# ProDoc_Custom_Keyboard_2025-10-20.net
KiCad netlist of a schematic drawn in EasyEDA Pro
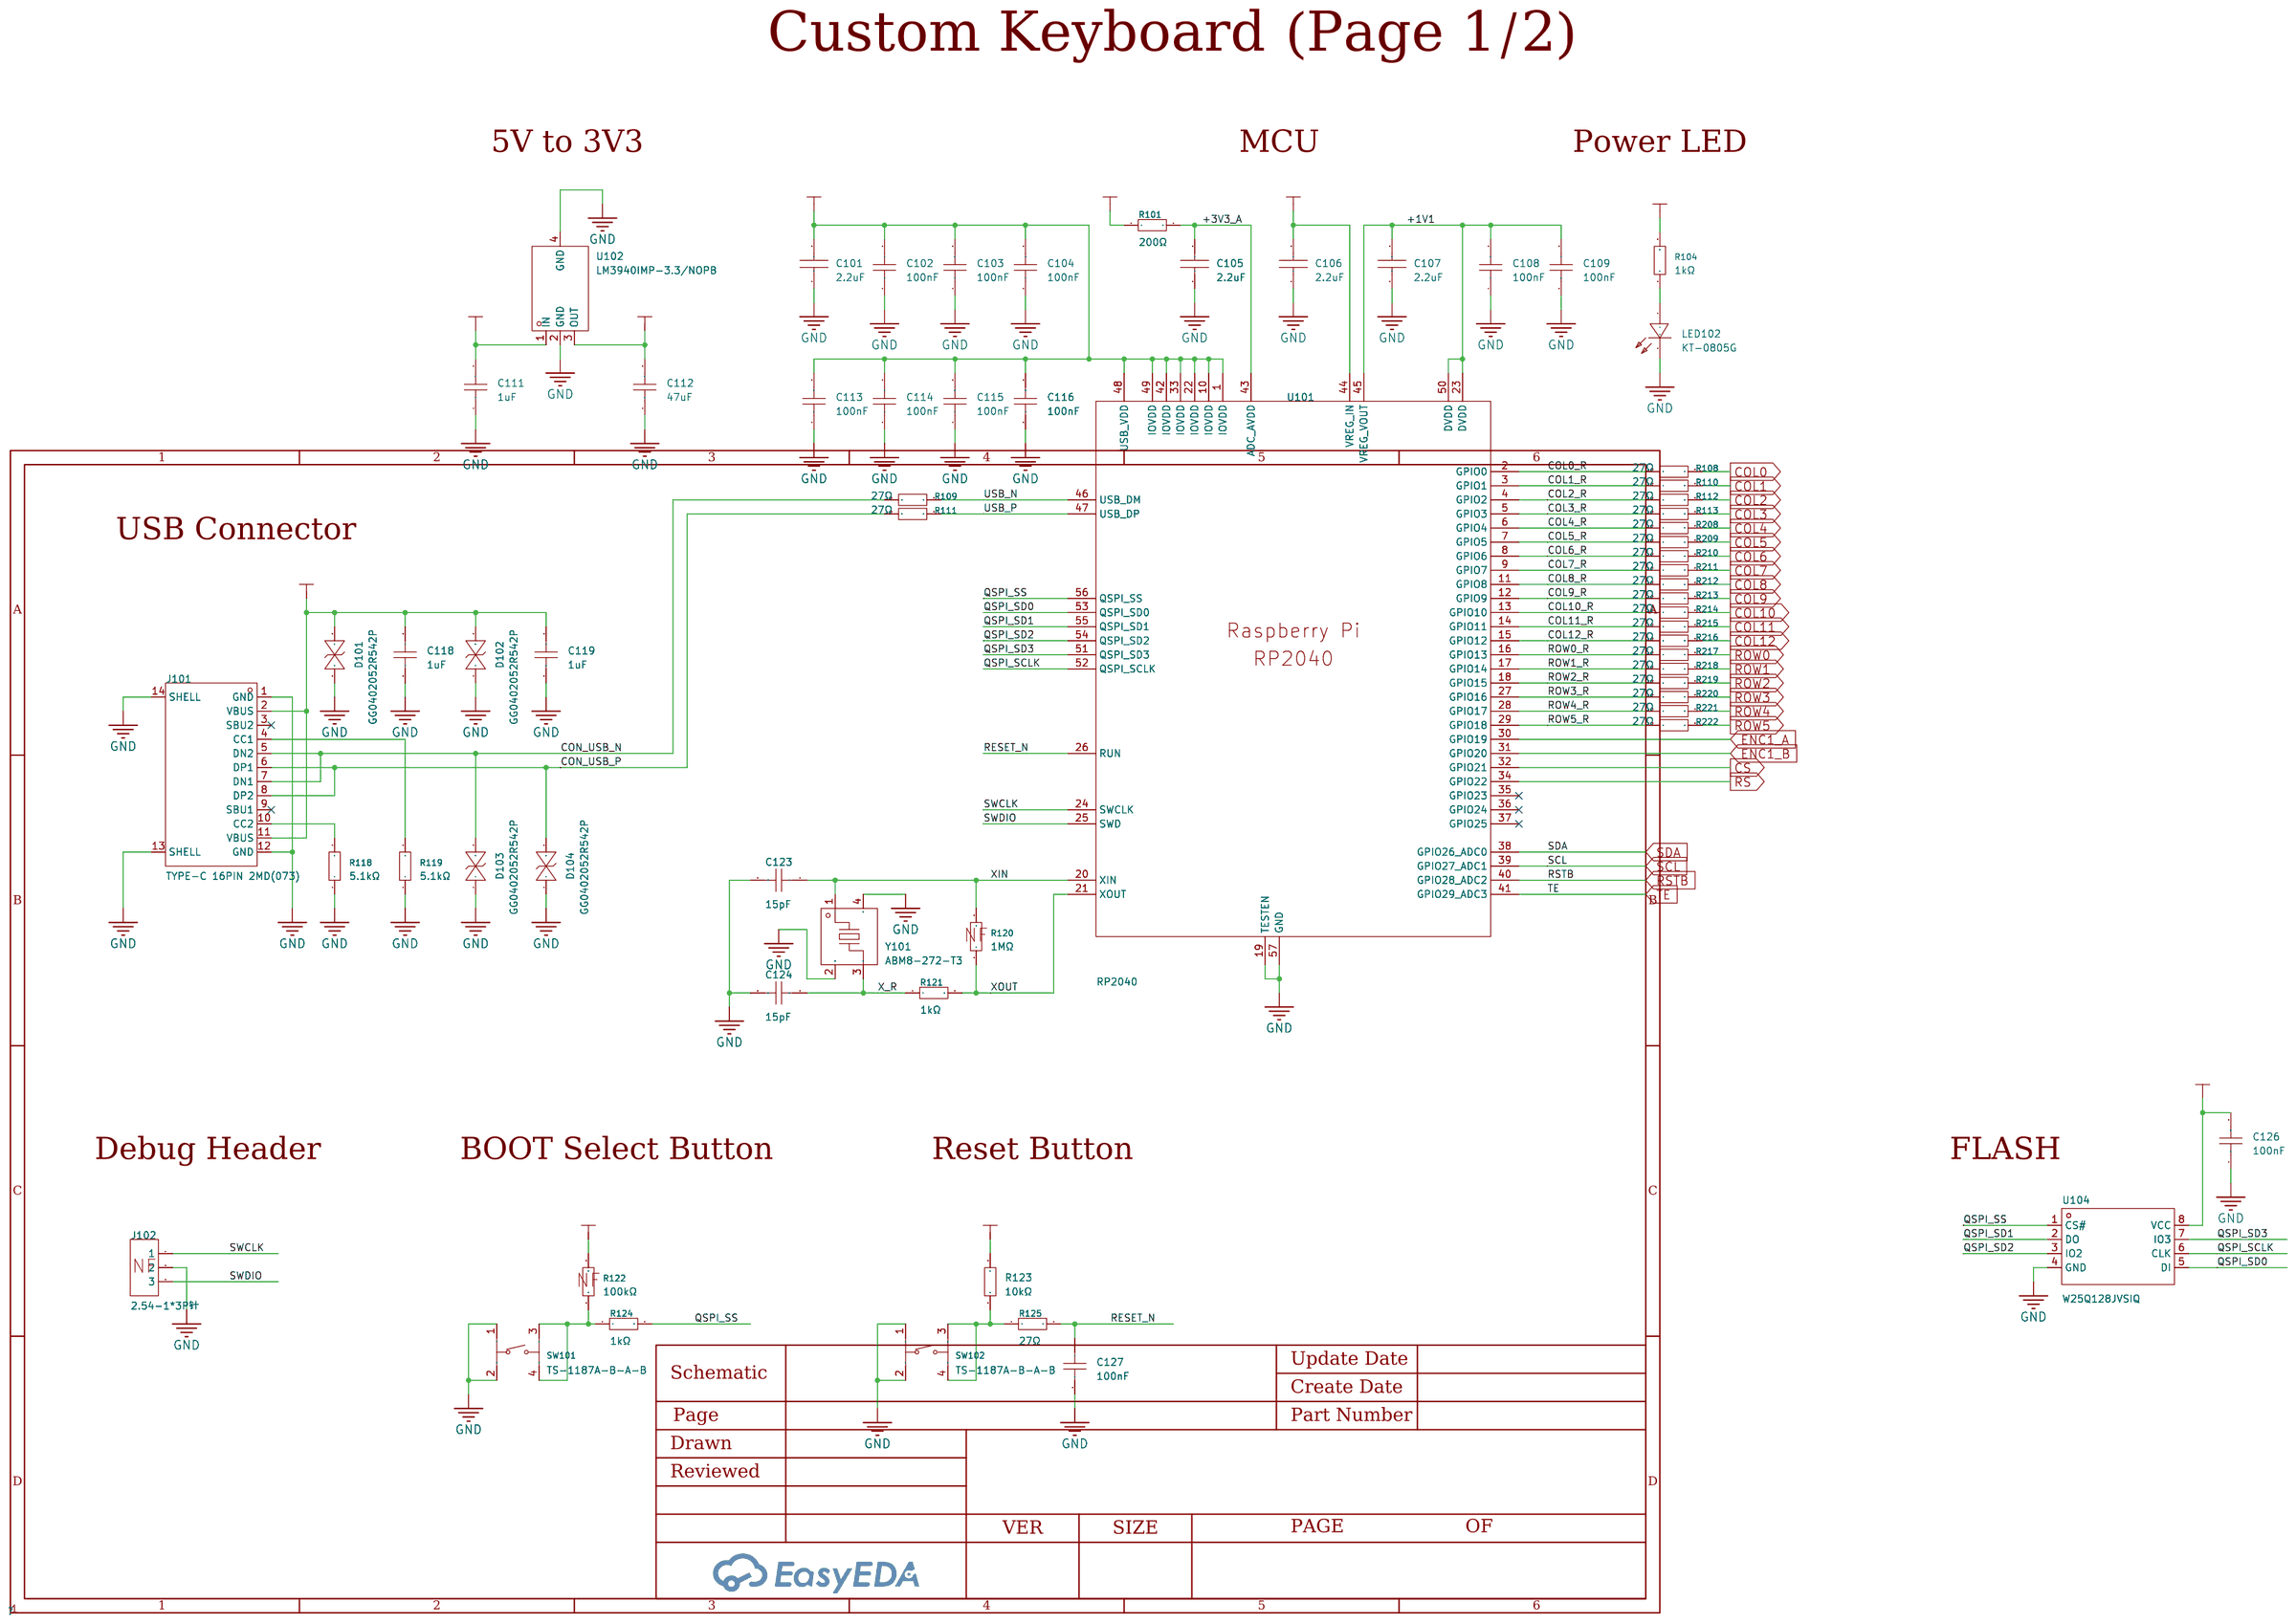
[diagram p0: MCU]
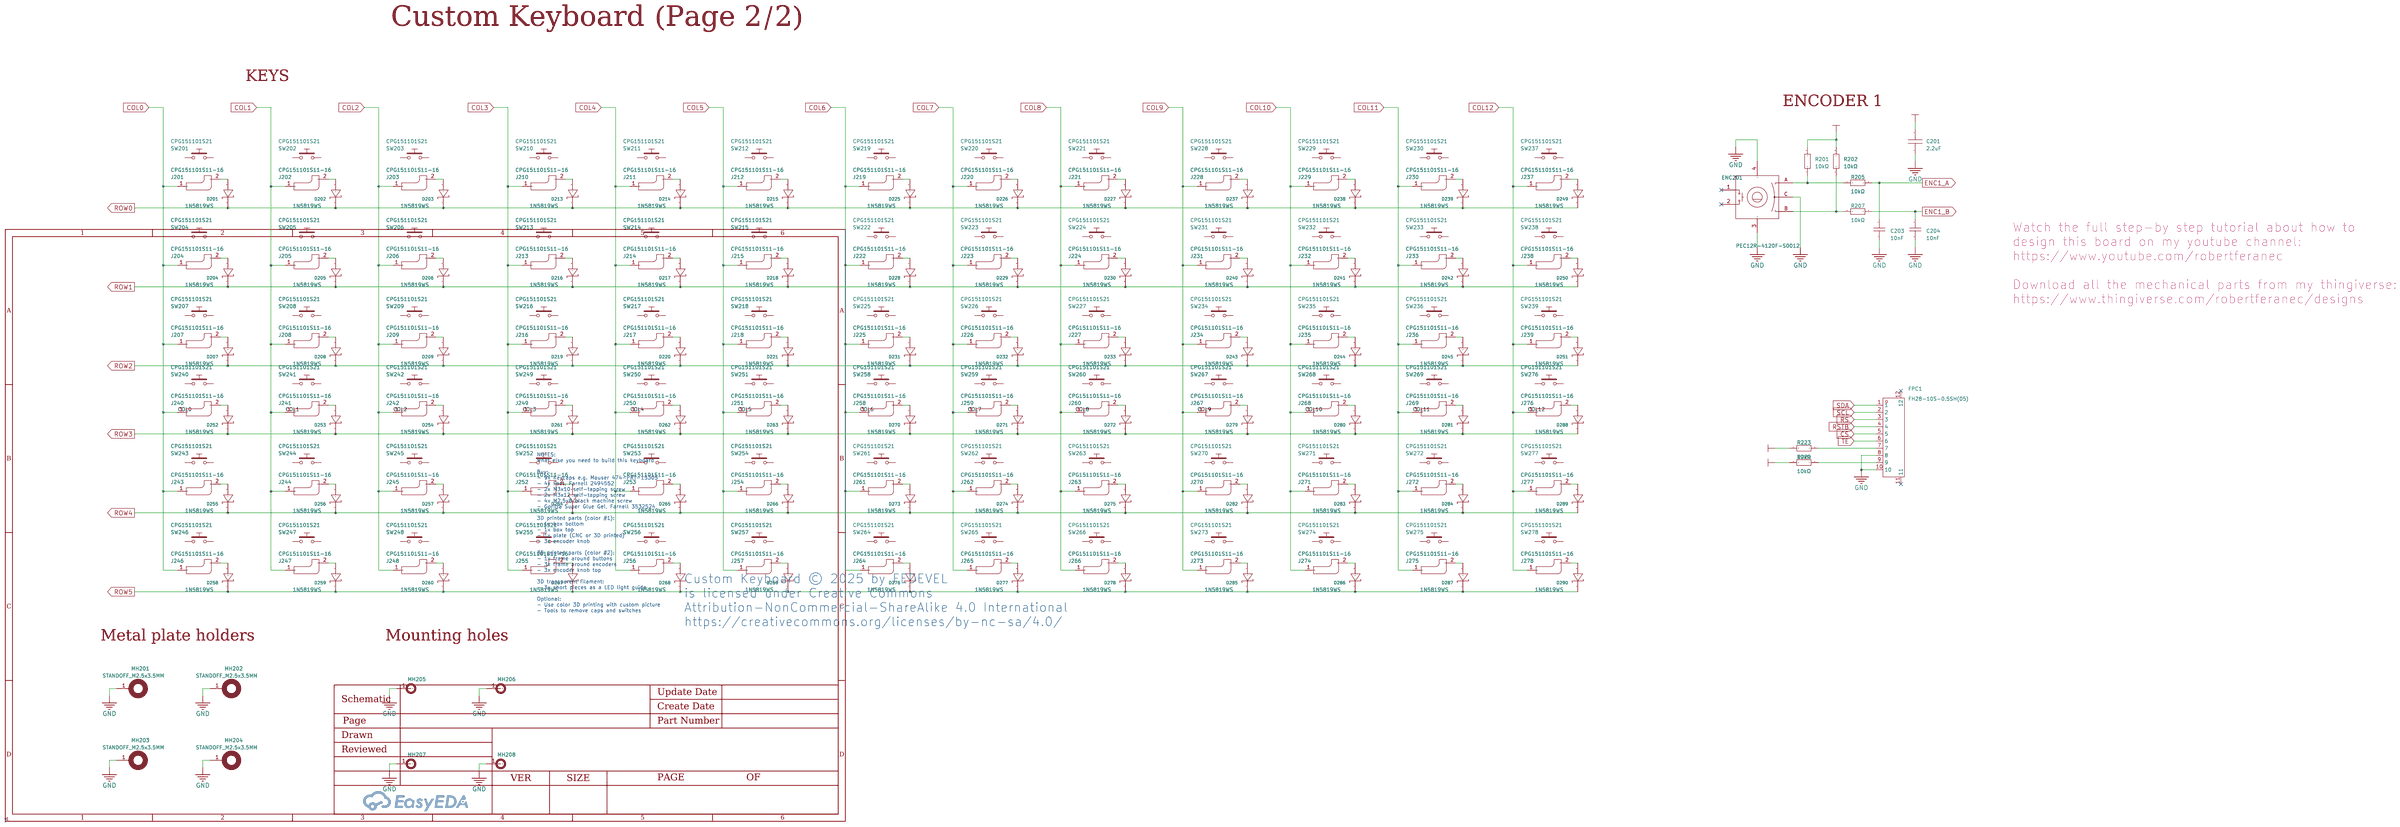
[diagram p1: OTHER]

(export (version "E")
  (design (tool "Eeschema 10.0.6"))
  (components
    (comp (ref "C101")
      (value "2.2uF")
      (footprint "easyedapro:C0402")
      (fields
        (field (name "Manufacturer Part") "CL05A225MQ5NSNC")
        (field (name "Manufacturer") "SAMSUNG(三星)")
      )
      (libsource (lib "easyedapro") (part "CL05A225MQ5NSNC"))
    )
    (comp (ref "C102")
      (value "100nF")
      (footprint "easyedapro:C0402")
      (fields
        (field (name "Manufacturer Part") "CL05B104KO5NNNC")
        (field (name "Manufacturer") "SAMSUNG(三星)")
      )
      (libsource (lib "easyedapro") (part "CL05B104KO5NNNC"))
    )
    (comp (ref "C103")
      (value "100nF")
      (footprint "easyedapro:C0402")
      (fields
        (field (name "Manufacturer Part") "CL05B104KO5NNNC")
        (field (name "Manufacturer") "SAMSUNG(三星)")
      )
      (libsource (lib "easyedapro") (part "CL05B104KO5NNNC"))
    )
    (comp (ref "C104")
      (value "100nF")
      (footprint "easyedapro:C0402")
      (fields
        (field (name "Manufacturer Part") "CL05B104KO5NNNC")
        (field (name "Manufacturer") "SAMSUNG(三星)")
      )
      (libsource (lib "easyedapro") (part "CL05B104KO5NNNC"))
    )
    (comp (ref "C105")
      (value "2.2uF")
      (footprint "easyedapro:C0402")
      (fields
        (field (name "Manufacturer Part") "CL05A225MQ5NSNC")
        (field (name "Manufacturer") "SAMSUNG(三星)")
      )
      (libsource (lib "easyedapro") (part "CL05A225MQ5NSNC"))
    )
    (comp (ref "C106")
      (value "2.2uF")
      (footprint "easyedapro:C0402")
      (fields
        (field (name "Manufacturer Part") "CL05A225MQ5NSNC")
        (field (name "Manufacturer") "SAMSUNG(三星)")
      )
      (libsource (lib "easyedapro") (part "CL05A225MQ5NSNC"))
    )
    (comp (ref "C107")
      (value "2.2uF")
      (footprint "easyedapro:C0402")
      (fields
        (field (name "Manufacturer Part") "CL05A225MQ5NSNC")
        (field (name "Manufacturer") "SAMSUNG(三星)")
      )
      (libsource (lib "easyedapro") (part "CL05A225MQ5NSNC"))
    )
    (comp (ref "C108")
      (value "100nF")
      (footprint "easyedapro:C0402")
      (fields
        (field (name "Manufacturer Part") "CL05B104KO5NNNC")
        (field (name "Manufacturer") "SAMSUNG(三星)")
      )
      (libsource (lib "easyedapro") (part "CL05B104KO5NNNC"))
    )
    (comp (ref "C109")
      (value "100nF")
      (footprint "easyedapro:C0402")
      (fields
        (field (name "Manufacturer Part") "CL05B104KO5NNNC")
        (field (name "Manufacturer") "SAMSUNG(三星)")
      )
      (libsource (lib "easyedapro") (part "CL05B104KO5NNNC"))
    )
    (comp (ref "C111")
      (value "1uF")
      (footprint "easyedapro:C0402")
      (fields
        (field (name "Manufacturer Part") "CL05A105KA5NQNC")
        (field (name "Manufacturer") "SAMSUNG(三星)")
      )
      (libsource (lib "easyedapro") (part "CL05A105KA5NQNC"))
    )
    (comp (ref "C112")
      (value "47uF")
      (footprint "easyedapro:C1206")
      (fields
        (field (name "Manufacturer Part") "CL31A476MPHNNNE")
        (field (name "Manufacturer") "SAMSUNG(三星)")
      )
      (libsource (lib "easyedapro") (part "CL31A476MPHNNNE"))
    )
    (comp (ref "C113")
      (value "100nF")
      (footprint "easyedapro:C0402")
      (fields
        (field (name "Manufacturer Part") "CL05B104KO5NNNC")
        (field (name "Manufacturer") "SAMSUNG(三星)")
      )
      (libsource (lib "easyedapro") (part "CL05B104KO5NNNC"))
    )
    (comp (ref "C114")
      (value "100nF")
      (footprint "easyedapro:C0402")
      (fields
        (field (name "Manufacturer Part") "CL05B104KO5NNNC")
        (field (name "Manufacturer") "SAMSUNG(三星)")
      )
      (libsource (lib "easyedapro") (part "CL05B104KO5NNNC"))
    )
    (comp (ref "C115")
      (value "100nF")
      (footprint "easyedapro:C0402")
      (fields
        (field (name "Manufacturer Part") "CL05B104KO5NNNC")
        (field (name "Manufacturer") "SAMSUNG(三星)")
      )
      (libsource (lib "easyedapro") (part "CL05B104KO5NNNC"))
    )
    (comp (ref "C116")
      (value "100nF")
      (footprint "easyedapro:C0402")
      (fields
        (field (name "Manufacturer Part") "CL05B104KO5NNNC")
        (field (name "Manufacturer") "SAMSUNG(三星)")
      )
      (libsource (lib "easyedapro") (part "CL05B104KO5NNNC"))
    )
    (comp (ref "C118")
      (value "1uF")
      (footprint "easyedapro:C0402")
      (fields
        (field (name "Manufacturer Part") "CL05A105KA5NQNC")
        (field (name "Manufacturer") "SAMSUNG(三星)")
      )
      (libsource (lib "easyedapro") (part "CL05A105KA5NQNC"))
    )
    (comp (ref "C119")
      (value "1uF")
      (footprint "easyedapro:C0402")
      (fields
        (field (name "Manufacturer Part") "CL05A105KA5NQNC")
        (field (name "Manufacturer") "SAMSUNG(三星)")
      )
      (libsource (lib "easyedapro") (part "CL05A105KA5NQNC"))
    )
    (comp (ref "C123")
      (value "15pF")
      (footprint "easyedapro:C0402")
      (fields
        (field (name "Manufacturer Part") "CL05C150JB5NNNC")
        (field (name "Manufacturer") "SAMSUNG(三星)")
      )
      (libsource (lib "easyedapro") (part "CL05C150JB5NNNC"))
    )
    (comp (ref "C124")
      (value "15pF")
      (footprint "easyedapro:C0402")
      (fields
        (field (name "Manufacturer Part") "CL05C150JB5NNNC")
        (field (name "Manufacturer") "SAMSUNG(三星)")
      )
      (libsource (lib "easyedapro") (part "CL05C150JB5NNNC"))
    )
    (comp (ref "C126")
      (value "100nF")
      (footprint "easyedapro:C0402")
      (fields
        (field (name "Manufacturer Part") "CL05B104KO5NNNC")
        (field (name "Manufacturer") "SAMSUNG(三星)")
      )
      (libsource (lib "easyedapro") (part "CL05B104KO5NNNC"))
    )
    (comp (ref "C127")
      (value "100nF")
      (footprint "easyedapro:C0402")
      (fields
        (field (name "Manufacturer Part") "CL05B104KO5NNNC")
        (field (name "Manufacturer") "SAMSUNG(三星)")
      )
      (libsource (lib "easyedapro") (part "CL05B104KO5NNNC"))
    )
    (comp (ref "D101")
      (value "GG0402052R542P")
      (footprint "easyedapro:D0402-BI")
      (fields (field (name "Manufacturer") "Kyocera AVX"))
      (libsource (lib "easyedapro") (part "GG0402052R542P"))
    )
    (comp (ref "D102")
      (value "GG0402052R542P")
      (footprint "easyedapro:D0402-BI")
      (fields (field (name "Manufacturer") "Kyocera AVX"))
      (libsource (lib "easyedapro") (part "GG0402052R542P"))
    )
    (comp (ref "D103")
      (value "GG0402052R542P")
      (footprint "easyedapro:D0402-BI")
      (fields (field (name "Manufacturer") "Kyocera AVX"))
      (libsource (lib "easyedapro") (part "GG0402052R542P"))
    )
    (comp (ref "D104")
      (value "GG0402052R542P")
      (footprint "easyedapro:D0402-BI")
      (fields (field (name "Manufacturer") "Kyocera AVX"))
      (libsource (lib "easyedapro") (part "GG0402052R542P"))
    )
    (comp (ref "J101")
      (value "TYPE-C 16PIN 2MD(073)")
      (footprint "easyedapro:USB-C-SMD_TYPE-C-6PIN-2MD-073")
      (fields (field (name "Manufacturer") "SHOU HAN(首韩)"))
      (libsource (lib "easyedapro") (part "TYPE-C 16PIN 2MD(073)"))
    )
    (comp (ref "J102")
      (value "2.54-1*3P针")
      (footprint "easyedapro:HDR-TH_3P-P2.54-V-M-1")
      (fields (field (name "Manufacturer") "BOOMELE(博穆精密)"))
      (libsource (lib "easyedapro") (part "Header-Male-2.54_1x3"))
    )
    (comp (ref "LED102")
      (value "KT-0805G")
      (footprint "easyedapro:LED0805-R-RD")
      (fields (field (name "Manufacturer") "KENTO"))
      (libsource (lib "easyedapro") (part "0805G (Green)"))
    )
    (comp (ref "R101")
      (value "200Ω")
      (footprint "easyedapro:R0402")
      (fields
        (field (name "Manufacturer Part") "0402WGF2000TCE")
        (field (name "Manufacturer") "UNI-ROYAL(厚声)")
      )
      (libsource (lib "easyedapro") (part "0402WGF2000TCE"))
    )
    (comp (ref "R104")
      (value "1kΩ")
      (footprint "easyedapro:R0402")
      (fields
        (field (name "Manufacturer Part") "0402WGF1001TCE")
        (field (name "Manufacturer") "UNI-ROYAL(厚声)")
      )
      (libsource (lib "easyedapro") (part "0402WGF1001TCE"))
    )
    (comp (ref "R108")
      (value "27Ω")
      (footprint "easyedapro:R0402")
      (fields
        (field (name "Manufacturer Part") "0402WGF270JTCE")
        (field (name "Manufacturer") "UNI-ROYAL(厚声)")
      )
      (libsource (lib "easyedapro") (part "0402WGF270JTCE"))
    )
    (comp (ref "R109")
      (value "27Ω")
      (footprint "easyedapro:R0402")
      (fields
        (field (name "Manufacturer Part") "0402WGF270JTCE")
        (field (name "Manufacturer") "UNI-ROYAL(厚声)")
      )
      (libsource (lib "easyedapro") (part "0402WGF270JTCE"))
    )
    (comp (ref "R110")
      (value "27Ω")
      (footprint "easyedapro:R0402")
      (fields
        (field (name "Manufacturer Part") "0402WGF270JTCE")
        (field (name "Manufacturer") "UNI-ROYAL(厚声)")
      )
      (libsource (lib "easyedapro") (part "0402WGF270JTCE"))
    )
    (comp (ref "R111")
      (value "27Ω")
      (footprint "easyedapro:R0402")
      (fields
        (field (name "Manufacturer Part") "0402WGF270JTCE")
        (field (name "Manufacturer") "UNI-ROYAL(厚声)")
      )
      (libsource (lib "easyedapro") (part "0402WGF270JTCE"))
    )
    (comp (ref "R112")
      (value "27Ω")
      (footprint "easyedapro:R0402")
      (fields
        (field (name "Manufacturer Part") "0402WGF270JTCE")
        (field (name "Manufacturer") "UNI-ROYAL(厚声)")
      )
      (libsource (lib "easyedapro") (part "0402WGF270JTCE"))
    )
    (comp (ref "R113")
      (value "27Ω")
      (footprint "easyedapro:R0402")
      (fields
        (field (name "Manufacturer Part") "0402WGF270JTCE")
        (field (name "Manufacturer") "UNI-ROYAL(厚声)")
      )
      (libsource (lib "easyedapro") (part "0402WGF270JTCE"))
    )
    (comp (ref "R118")
      (value "5.1kΩ")
      (footprint "easyedapro:R0402")
      (fields
        (field (name "Manufacturer Part") "0402WGF5101TCE")
        (field (name "Manufacturer") "UNI-ROYAL(厚声)")
      )
      (libsource (lib "easyedapro") (part "0402WGF5101TCE"))
    )
    (comp (ref "R119")
      (value "5.1kΩ")
      (footprint "easyedapro:R0402")
      (fields
        (field (name "Manufacturer Part") "0402WGF5101TCE")
        (field (name "Manufacturer") "UNI-ROYAL(厚声)")
      )
      (libsource (lib "easyedapro") (part "0402WGF5101TCE"))
    )
    (comp (ref "R120")
      (value "1MΩ")
      (footprint "easyedapro:R0402")
      (fields
        (field (name "Manufacturer Part") "0402WGF1004TCE")
        (field (name "Manufacturer") "UNI-ROYAL(厚声)")
      )
      (libsource (lib "easyedapro") (part "0402WGF1004TCE"))
    )
    (comp (ref "R121")
      (value "1kΩ")
      (footprint "easyedapro:R0402")
      (fields
        (field (name "Manufacturer Part") "0402WGF1001TCE")
        (field (name "Manufacturer") "UNI-ROYAL(厚声)")
      )
      (libsource (lib "easyedapro") (part "0402WGF1001TCE"))
    )
    (comp (ref "R122")
      (value "100kΩ")
      (footprint "easyedapro:R0402")
      (fields
        (field (name "Manufacturer Part") "0402WGF1003TCE")
        (field (name "Manufacturer") "UNI-ROYAL(厚声)")
      )
      (libsource (lib "easyedapro") (part "0402WGF1003TCE"))
    )
    (comp (ref "R123")
      (value "10kΩ")
      (footprint "easyedapro:R0402")
      (fields
        (field (name "Manufacturer Part") "0402WGF1002TCE")
        (field (name "Manufacturer") "UNI-ROYAL(厚声)")
      )
      (libsource (lib "easyedapro") (part "0402WGF1002TCE"))
    )
    (comp (ref "R124")
      (value "1kΩ")
      (footprint "easyedapro:R0402")
      (fields
        (field (name "Manufacturer Part") "0402WGF1001TCE")
        (field (name "Manufacturer") "UNI-ROYAL(厚声)")
      )
      (libsource (lib "easyedapro") (part "0402WGF1001TCE"))
    )
    (comp (ref "R125")
      (value "27Ω")
      (footprint "easyedapro:R0402")
      (fields
        (field (name "Manufacturer Part") "0402WGF270JTCE")
        (field (name "Manufacturer") "UNI-ROYAL(厚声)")
      )
      (libsource (lib "easyedapro") (part "0402WGF270JTCE"))
    )
    (comp (ref "R208")
      (value "27Ω")
      (footprint "easyedapro:R0402")
      (fields
        (field (name "Manufacturer Part") "0402WGF270JTCE")
        (field (name "Manufacturer") "UNI-ROYAL(厚声)")
      )
      (libsource (lib "easyedapro") (part "0402WGF270JTCE"))
    )
    (comp (ref "R209")
      (value "27Ω")
      (footprint "easyedapro:R0402")
      (fields
        (field (name "Manufacturer Part") "0402WGF270JTCE")
        (field (name "Manufacturer") "UNI-ROYAL(厚声)")
      )
      (libsource (lib "easyedapro") (part "0402WGF270JTCE"))
    )
    (comp (ref "R210")
      (value "27Ω")
      (footprint "easyedapro:R0402")
      (fields
        (field (name "Manufacturer Part") "0402WGF270JTCE")
        (field (name "Manufacturer") "UNI-ROYAL(厚声)")
      )
      (libsource (lib "easyedapro") (part "0402WGF270JTCE"))
    )
    (comp (ref "R211")
      (value "27Ω")
      (footprint "easyedapro:R0402")
      (fields
        (field (name "Manufacturer Part") "0402WGF270JTCE")
        (field (name "Manufacturer") "UNI-ROYAL(厚声)")
      )
      (libsource (lib "easyedapro") (part "0402WGF270JTCE"))
    )
    (comp (ref "R212")
      (value "27Ω")
      (footprint "easyedapro:R0402")
      (fields
        (field (name "Manufacturer Part") "0402WGF270JTCE")
        (field (name "Manufacturer") "UNI-ROYAL(厚声)")
      )
      (libsource (lib "easyedapro") (part "0402WGF270JTCE"))
    )
    (comp (ref "R213")
      (value "27Ω")
      (footprint "easyedapro:R0402")
      (fields
        (field (name "Manufacturer Part") "0402WGF270JTCE")
        (field (name "Manufacturer") "UNI-ROYAL(厚声)")
      )
      (libsource (lib "easyedapro") (part "0402WGF270JTCE"))
    )
    (comp (ref "R214")
      (value "27Ω")
      (footprint "easyedapro:R0402")
      (fields
        (field (name "Manufacturer Part") "0402WGF270JTCE")
        (field (name "Manufacturer") "UNI-ROYAL(厚声)")
      )
      (libsource (lib "easyedapro") (part "0402WGF270JTCE"))
    )
    (comp (ref "R215")
      (value "27Ω")
      (footprint "easyedapro:R0402")
      (fields
        (field (name "Manufacturer Part") "0402WGF270JTCE")
        (field (name "Manufacturer") "UNI-ROYAL(厚声)")
      )
      (libsource (lib "easyedapro") (part "0402WGF270JTCE"))
    )
    (comp (ref "R216")
      (value "27Ω")
      (footprint "easyedapro:R0402")
      (fields
        (field (name "Manufacturer Part") "0402WGF270JTCE")
        (field (name "Manufacturer") "UNI-ROYAL(厚声)")
      )
      (libsource (lib "easyedapro") (part "0402WGF270JTCE"))
    )
    (comp (ref "R217")
      (value "27Ω")
      (footprint "easyedapro:R0402")
      (fields
        (field (name "Manufacturer Part") "0402WGF270JTCE")
        (field (name "Manufacturer") "UNI-ROYAL(厚声)")
      )
      (libsource (lib "easyedapro") (part "0402WGF270JTCE"))
    )
    (comp (ref "R218")
      (value "27Ω")
      (footprint "easyedapro:R0402")
      (fields
        (field (name "Manufacturer Part") "0402WGF270JTCE")
        (field (name "Manufacturer") "UNI-ROYAL(厚声)")
      )
      (libsource (lib "easyedapro") (part "0402WGF270JTCE"))
    )
    (comp (ref "R219")
      (value "27Ω")
      (footprint "easyedapro:R0402")
      (fields
        (field (name "Manufacturer Part") "0402WGF270JTCE")
        (field (name "Manufacturer") "UNI-ROYAL(厚声)")
      )
      (libsource (lib "easyedapro") (part "0402WGF270JTCE"))
    )
    (comp (ref "R220")
      (value "27Ω")
      (footprint "easyedapro:R0402")
      (fields
        (field (name "Manufacturer Part") "0402WGF270JTCE")
        (field (name "Manufacturer") "UNI-ROYAL(厚声)")
      )
      (libsource (lib "easyedapro") (part "0402WGF270JTCE"))
    )
    (comp (ref "R221")
      (value "27Ω")
      (footprint "easyedapro:R0402")
      (fields
        (field (name "Manufacturer Part") "0402WGF270JTCE")
        (field (name "Manufacturer") "UNI-ROYAL(厚声)")
      )
      (libsource (lib "easyedapro") (part "0402WGF270JTCE"))
    )
    (comp (ref "R222")
      (value "27Ω")
      (footprint "easyedapro:R0402")
      (fields
        (field (name "Manufacturer Part") "0402WGF270JTCE")
        (field (name "Manufacturer") "UNI-ROYAL(厚声)")
      )
      (libsource (lib "easyedapro") (part "0402WGF270JTCE"))
    )
    (comp (ref "SW101")
      (value "TS-1187A-B-A-B")
      (footprint "easyedapro:SW-SMD_4P-L5.1-W5.1-P3.70-LS6.5-TL-2")
      (fields (field (name "Manufacturer") "XKB Connectivity(中国星坤)"))
      (libsource (lib "easyedapro") (part "TS-1187A-B-A-B"))
    )
    (comp (ref "SW102")
      (value "TS-1187A-B-A-B")
      (footprint "easyedapro:SW-SMD_4P-L5.1-W5.1-P3.70-LS6.5-TL-2")
      (fields (field (name "Manufacturer") "XKB Connectivity(中国星坤)"))
      (libsource (lib "easyedapro") (part "TS-1187A-B-A-B"))
    )
    (comp (ref "U101")
      (value "RP2040")
      (footprint "easyedapro:LQFN-56_L7.0-W7.0-P0.4-EP_1")
      (fields (field (name "Manufacturer") "Raspberry Pi(树莓派)"))
      (libsource (lib "easyedapro") (part "RP2040_C2040_RF_v1.0"))
    )
    (comp (ref "U102")
      (value "LM3940IMP-3.3/NOPB")
      (footprint "easyedapro:SOT-223_L6.5-W3.5-P2.30-LS7.0-BR")
      (fields (field (name "Manufacturer") "TI(德州仪器)"))
      (libsource (lib "easyedapro") (part "LM3940IMP-3.3/NOPB"))
    )
    (comp (ref "U104")
      (value "W25Q128JVSIQ")
      (footprint "easyedapro:SOIC-8_L5.3-W5.3-P1.27-LS8.0-BL")
      (fields (field (name "Manufacturer") "WINBOND(华邦)"))
      (libsource (lib "easyedapro") (part "W25Q128JVSIQTR"))
    )
    (comp (ref "Y101")
      (value "ABM8-272-T3")
      (footprint "easyedapro:CRYSTAL-SMD_4P-L3.2-W2.5-BL")
      (fields (field (name "Manufacturer") "ABRACON"))
      (libsource (lib "easyedapro") (part "ABM8-272-T3_C20625731"))
    )
    (comp (ref "C201")
      (value "2.2uF")
      (footprint "easyedapro:C0402")
      (fields
        (field (name "Manufacturer Part") "CL05A225MQ5NSNC")
        (field (name "Manufacturer") "SAMSUNG(三星)")
      )
      (libsource (lib "easyedapro") (part "CL05A225MQ5NSNC"))
    )
    (comp (ref "C203")
      (value "10nF")
      (footprint "easyedapro:C0402")
      (fields
        (field (name "Manufacturer Part") "CL05B103KB5NNNC")
        (field (name "Manufacturer") "SAMSUNG(三星)")
      )
      (libsource (lib "easyedapro") (part "CL05B103KB5NNNC"))
    )
    (comp (ref "C204")
      (value "10nF")
      (footprint "easyedapro:C0402")
      (fields
        (field (name "Manufacturer Part") "CL05B103KB5NNNC")
        (field (name "Manufacturer") "SAMSUNG(三星)")
      )
      (libsource (lib "easyedapro") (part "CL05B103KB5NNNC"))
    )
    (comp (ref "D201")
      (value "1N5819WS")
      (footprint "easyedapro:SOD-323_L1.8-W1.3-LS2.5-RD")
      (description "Forward Voltage (Vf@If):600mV@1A Reverse Voltage (Vr):40V Average Rectified Current (Io):1A")
      (fields (field (name "Manufacturer") "Hottech(合科泰)"))
      (libsource (lib "easyedapro") (part "1N5819WS"))
    )
    (comp (ref "D202")
      (value "1N5819WS")
      (footprint "easyedapro:SOD-323_L1.8-W1.3-LS2.5-RD")
      (description "Forward Voltage (Vf@If):600mV@1A Reverse Voltage (Vr):40V Average Rectified Current (Io):1A")
      (fields (field (name "Manufacturer") "Hottech(合科泰)"))
      (libsource (lib "easyedapro") (part "1N5819WS"))
    )
    (comp (ref "D203")
      (value "1N5819WS")
      (footprint "easyedapro:SOD-323_L1.8-W1.3-LS2.5-RD")
      (description "Forward Voltage (Vf@If):600mV@1A Reverse Voltage (Vr):40V Average Rectified Current (Io):1A")
      (fields (field (name "Manufacturer") "Hottech(合科泰)"))
      (libsource (lib "easyedapro") (part "1N5819WS"))
    )
    (comp (ref "D204")
      (value "1N5819WS")
      (footprint "easyedapro:SOD-323_L1.8-W1.3-LS2.5-RD")
      (description "Forward Voltage (Vf@If):600mV@1A Reverse Voltage (Vr):40V Average Rectified Current (Io):1A")
      (fields (field (name "Manufacturer") "Hottech(合科泰)"))
      (libsource (lib "easyedapro") (part "1N5819WS"))
    )
    (comp (ref "D205")
      (value "1N5819WS")
      (footprint "easyedapro:SOD-323_L1.8-W1.3-LS2.5-RD")
      (description "Forward Voltage (Vf@If):600mV@1A Reverse Voltage (Vr):40V Average Rectified Current (Io):1A")
      (fields (field (name "Manufacturer") "Hottech(合科泰)"))
      (libsource (lib "easyedapro") (part "1N5819WS"))
    )
    (comp (ref "D206")
      (value "1N5819WS")
      (footprint "easyedapro:SOD-323_L1.8-W1.3-LS2.5-RD")
      (description "Forward Voltage (Vf@If):600mV@1A Reverse Voltage (Vr):40V Average Rectified Current (Io):1A")
      (fields (field (name "Manufacturer") "Hottech(合科泰)"))
      (libsource (lib "easyedapro") (part "1N5819WS"))
    )
    (comp (ref "D207")
      (value "1N5819WS")
      (footprint "easyedapro:SOD-323_L1.8-W1.3-LS2.5-RD")
      (description "Forward Voltage (Vf@If):600mV@1A Reverse Voltage (Vr):40V Average Rectified Current (Io):1A")
      (fields (field (name "Manufacturer") "Hottech(合科泰)"))
      (libsource (lib "easyedapro") (part "1N5819WS"))
    )
    (comp (ref "D208")
      (value "1N5819WS")
      (footprint "easyedapro:SOD-323_L1.8-W1.3-LS2.5-RD")
      (description "Forward Voltage (Vf@If):600mV@1A Reverse Voltage (Vr):40V Average Rectified Current (Io):1A")
      (fields (field (name "Manufacturer") "Hottech(合科泰)"))
      (libsource (lib "easyedapro") (part "1N5819WS"))
    )
    (comp (ref "D209")
      (value "1N5819WS")
      (footprint "easyedapro:SOD-323_L1.8-W1.3-LS2.5-RD")
      (description "Forward Voltage (Vf@If):600mV@1A Reverse Voltage (Vr):40V Average Rectified Current (Io):1A")
      (fields (field (name "Manufacturer") "Hottech(合科泰)"))
      (libsource (lib "easyedapro") (part "1N5819WS"))
    )
    (comp (ref "D213")
      (value "1N5819WS")
      (footprint "easyedapro:SOD-323_L1.8-W1.3-LS2.5-RD")
      (description "Forward Voltage (Vf@If):600mV@1A Reverse Voltage (Vr):40V Average Rectified Current (Io):1A")
      (fields (field (name "Manufacturer") "Hottech(合科泰)"))
      (libsource (lib "easyedapro") (part "1N5819WS"))
    )
    (comp (ref "D214")
      (value "1N5819WS")
      (footprint "easyedapro:SOD-323_L1.8-W1.3-LS2.5-RD")
      (description "Forward Voltage (Vf@If):600mV@1A Reverse Voltage (Vr):40V Average Rectified Current (Io):1A")
      (fields (field (name "Manufacturer") "Hottech(合科泰)"))
      (libsource (lib "easyedapro") (part "1N5819WS"))
    )
    (comp (ref "D215")
      (value "1N5819WS")
      (footprint "easyedapro:SOD-323_L1.8-W1.3-LS2.5-RD")
      (description "Forward Voltage (Vf@If):600mV@1A Reverse Voltage (Vr):40V Average Rectified Current (Io):1A")
      (fields (field (name "Manufacturer") "Hottech(合科泰)"))
      (libsource (lib "easyedapro") (part "1N5819WS"))
    )
    (comp (ref "D216")
      (value "1N5819WS")
      (footprint "easyedapro:SOD-323_L1.8-W1.3-LS2.5-RD")
      (description "Forward Voltage (Vf@If):600mV@1A Reverse Voltage (Vr):40V Average Rectified Current (Io):1A")
      (fields (field (name "Manufacturer") "Hottech(合科泰)"))
      (libsource (lib "easyedapro") (part "1N5819WS"))
    )
    (comp (ref "D217")
      (value "1N5819WS")
      (footprint "easyedapro:SOD-323_L1.8-W1.3-LS2.5-RD")
      (description "Forward Voltage (Vf@If):600mV@1A Reverse Voltage (Vr):40V Average Rectified Current (Io):1A")
      (fields (field (name "Manufacturer") "Hottech(合科泰)"))
      (libsource (lib "easyedapro") (part "1N5819WS"))
    )
    (comp (ref "D218")
      (value "1N5819WS")
      (footprint "easyedapro:SOD-323_L1.8-W1.3-LS2.5-RD")
      (description "Forward Voltage (Vf@If):600mV@1A Reverse Voltage (Vr):40V Average Rectified Current (Io):1A")
      (fields (field (name "Manufacturer") "Hottech(合科泰)"))
      (libsource (lib "easyedapro") (part "1N5819WS"))
    )
    (comp (ref "D219")
      (value "1N5819WS")
      (footprint "easyedapro:SOD-323_L1.8-W1.3-LS2.5-RD")
      (description "Forward Voltage (Vf@If):600mV@1A Reverse Voltage (Vr):40V Average Rectified Current (Io):1A")
      (fields (field (name "Manufacturer") "Hottech(合科泰)"))
      (libsource (lib "easyedapro") (part "1N5819WS"))
    )
    (comp (ref "D220")
      (value "1N5819WS")
      (footprint "easyedapro:SOD-323_L1.8-W1.3-LS2.5-RD")
      (description "Forward Voltage (Vf@If):600mV@1A Reverse Voltage (Vr):40V Average Rectified Current (Io):1A")
      (fields (field (name "Manufacturer") "Hottech(合科泰)"))
      (libsource (lib "easyedapro") (part "1N5819WS"))
    )
    (comp (ref "D221")
      (value "1N5819WS")
      (footprint "easyedapro:SOD-323_L1.8-W1.3-LS2.5-RD")
      (description "Forward Voltage (Vf@If):600mV@1A Reverse Voltage (Vr):40V Average Rectified Current (Io):1A")
      (fields (field (name "Manufacturer") "Hottech(合科泰)"))
      (libsource (lib "easyedapro") (part "1N5819WS"))
    )
    (comp (ref "D225")
      (value "1N5819WS")
      (footprint "easyedapro:SOD-323_L1.8-W1.3-LS2.5-RD")
      (description "Forward Voltage (Vf@If):600mV@1A Reverse Voltage (Vr):40V Average Rectified Current (Io):1A")
      (fields (field (name "Manufacturer") "Hottech(合科泰)"))
      (libsource (lib "easyedapro") (part "1N5819WS"))
    )
    (comp (ref "D226")
      (value "1N5819WS")
      (footprint "easyedapro:SOD-323_L1.8-W1.3-LS2.5-RD")
      (description "Forward Voltage (Vf@If):600mV@1A Reverse Voltage (Vr):40V Average Rectified Current (Io):1A")
      (fields (field (name "Manufacturer") "Hottech(合科泰)"))
      (libsource (lib "easyedapro") (part "1N5819WS"))
    )
    (comp (ref "D227")
      (value "1N5819WS")
      (footprint "easyedapro:SOD-323_L1.8-W1.3-LS2.5-RD")
      (description "Forward Voltage (Vf@If):600mV@1A Reverse Voltage (Vr):40V Average Rectified Current (Io):1A")
      (fields (field (name "Manufacturer") "Hottech(合科泰)"))
      (libsource (lib "easyedapro") (part "1N5819WS"))
    )
    (comp (ref "D228")
      (value "1N5819WS")
      (footprint "easyedapro:SOD-323_L1.8-W1.3-LS2.5-RD")
      (description "Forward Voltage (Vf@If):600mV@1A Reverse Voltage (Vr):40V Average Rectified Current (Io):1A")
      (fields (field (name "Manufacturer") "Hottech(合科泰)"))
      (libsource (lib "easyedapro") (part "1N5819WS"))
    )
    (comp (ref "D229")
      (value "1N5819WS")
      (footprint "easyedapro:SOD-323_L1.8-W1.3-LS2.5-RD")
      (description "Forward Voltage (Vf@If):600mV@1A Reverse Voltage (Vr):40V Average Rectified Current (Io):1A")
      (fields (field (name "Manufacturer") "Hottech(合科泰)"))
      (libsource (lib "easyedapro") (part "1N5819WS"))
    )
    (comp (ref "D230")
      (value "1N5819WS")
      (footprint "easyedapro:SOD-323_L1.8-W1.3-LS2.5-RD")
      (description "Forward Voltage (Vf@If):600mV@1A Reverse Voltage (Vr):40V Average Rectified Current (Io):1A")
      (fields (field (name "Manufacturer") "Hottech(合科泰)"))
      (libsource (lib "easyedapro") (part "1N5819WS"))
    )
    (comp (ref "D231")
      (value "1N5819WS")
      (footprint "easyedapro:SOD-323_L1.8-W1.3-LS2.5-RD")
      (description "Forward Voltage (Vf@If):600mV@1A Reverse Voltage (Vr):40V Average Rectified Current (Io):1A")
      (fields (field (name "Manufacturer") "Hottech(合科泰)"))
      (libsource (lib "easyedapro") (part "1N5819WS"))
    )
    (comp (ref "D232")
      (value "1N5819WS")
      (footprint "easyedapro:SOD-323_L1.8-W1.3-LS2.5-RD")
      (description "Forward Voltage (Vf@If):600mV@1A Reverse Voltage (Vr):40V Average Rectified Current (Io):1A")
      (fields (field (name "Manufacturer") "Hottech(合科泰)"))
      (libsource (lib "easyedapro") (part "1N5819WS"))
    )
    (comp (ref "D233")
      (value "1N5819WS")
      (footprint "easyedapro:SOD-323_L1.8-W1.3-LS2.5-RD")
      (description "Forward Voltage (Vf@If):600mV@1A Reverse Voltage (Vr):40V Average Rectified Current (Io):1A")
      (fields (field (name "Manufacturer") "Hottech(合科泰)"))
      (libsource (lib "easyedapro") (part "1N5819WS"))
    )
    (comp (ref "D237")
      (value "1N5819WS")
      (footprint "easyedapro:SOD-323_L1.8-W1.3-LS2.5-RD")
      (description "Forward Voltage (Vf@If):600mV@1A Reverse Voltage (Vr):40V Average Rectified Current (Io):1A")
      (fields (field (name "Manufacturer") "Hottech(合科泰)"))
      (libsource (lib "easyedapro") (part "1N5819WS"))
    )
    (comp (ref "D238")
      (value "1N5819WS")
      (footprint "easyedapro:SOD-323_L1.8-W1.3-LS2.5-RD")
      (description "Forward Voltage (Vf@If):600mV@1A Reverse Voltage (Vr):40V Average Rectified Current (Io):1A")
      (fields (field (name "Manufacturer") "Hottech(合科泰)"))
      (libsource (lib "easyedapro") (part "1N5819WS"))
    )
    (comp (ref "D239")
      (value "1N5819WS")
      (footprint "easyedapro:SOD-323_L1.8-W1.3-LS2.5-RD")
      (description "Forward Voltage (Vf@If):600mV@1A Reverse Voltage (Vr):40V Average Rectified Current (Io):1A")
      (fields (field (name "Manufacturer") "Hottech(合科泰)"))
      (libsource (lib "easyedapro") (part "1N5819WS"))
    )
    (comp (ref "D240")
      (value "1N5819WS")
      (footprint "easyedapro:SOD-323_L1.8-W1.3-LS2.5-RD")
      (description "Forward Voltage (Vf@If):600mV@1A Reverse Voltage (Vr):40V Average Rectified Current (Io):1A")
      (fields (field (name "Manufacturer") "Hottech(合科泰)"))
      (libsource (lib "easyedapro") (part "1N5819WS"))
    )
    (comp (ref "D241")
      (value "1N5819WS")
      (footprint "easyedapro:SOD-323_L1.8-W1.3-LS2.5-RD")
      (description "Forward Voltage (Vf@If):600mV@1A Reverse Voltage (Vr):40V Average Rectified Current (Io):1A")
      (fields (field (name "Manufacturer") "Hottech(合科泰)"))
      (libsource (lib "easyedapro") (part "1N5819WS"))
    )
    (comp (ref "D242")
      (value "1N5819WS")
      (footprint "easyedapro:SOD-323_L1.8-W1.3-LS2.5-RD")
      (description "Forward Voltage (Vf@If):600mV@1A Reverse Voltage (Vr):40V Average Rectified Current (Io):1A")
      (fields (field (name "Manufacturer") "Hottech(合科泰)"))
      (libsource (lib "easyedapro") (part "1N5819WS"))
    )
    (comp (ref "D243")
      (value "1N5819WS")
      (footprint "easyedapro:SOD-323_L1.8-W1.3-LS2.5-RD")
      (description "Forward Voltage (Vf@If):600mV@1A Reverse Voltage (Vr):40V Average Rectified Current (Io):1A")
      (fields (field (name "Manufacturer") "Hottech(合科泰)"))
      (libsource (lib "easyedapro") (part "1N5819WS"))
    )
    (comp (ref "D244")
      (value "1N5819WS")
      (footprint "easyedapro:SOD-323_L1.8-W1.3-LS2.5-RD")
      (description "Forward Voltage (Vf@If):600mV@1A Reverse Voltage (Vr):40V Average Rectified Current (Io):1A")
      (fields (field (name "Manufacturer") "Hottech(合科泰)"))
      (libsource (lib "easyedapro") (part "1N5819WS"))
    )
    (comp (ref "D245")
      (value "1N5819WS")
      (footprint "easyedapro:SOD-323_L1.8-W1.3-LS2.5-RD")
      (description "Forward Voltage (Vf@If):600mV@1A Reverse Voltage (Vr):40V Average Rectified Current (Io):1A")
      (fields (field (name "Manufacturer") "Hottech(合科泰)"))
      (libsource (lib "easyedapro") (part "1N5819WS"))
    )
    (comp (ref "D249")
      (value "1N5819WS")
      (footprint "easyedapro:SOD-323_L1.8-W1.3-LS2.5-RD")
      (description "Forward Voltage (Vf@If):600mV@1A Reverse Voltage (Vr):40V Average Rectified Current (Io):1A")
      (fields (field (name "Manufacturer") "Hottech(合科泰)"))
      (libsource (lib "easyedapro") (part "1N5819WS"))
    )
    (comp (ref "D250")
      (value "1N5819WS")
      (footprint "easyedapro:SOD-323_L1.8-W1.3-LS2.5-RD")
      (description "Forward Voltage (Vf@If):600mV@1A Reverse Voltage (Vr):40V Average Rectified Current (Io):1A")
      (fields (field (name "Manufacturer") "Hottech(合科泰)"))
      (libsource (lib "easyedapro") (part "1N5819WS"))
    )
    (comp (ref "D251")
      (value "1N5819WS")
      (footprint "easyedapro:SOD-323_L1.8-W1.3-LS2.5-RD")
      (description "Forward Voltage (Vf@If):600mV@1A Reverse Voltage (Vr):40V Average Rectified Current (Io):1A")
      (fields (field (name "Manufacturer") "Hottech(合科泰)"))
      (libsource (lib "easyedapro") (part "1N5819WS"))
    )
    (comp (ref "D252")
      (value "1N5819WS")
      (footprint "easyedapro:SOD-323_L1.8-W1.3-LS2.5-RD")
      (description "Forward Voltage (Vf@If):600mV@1A Reverse Voltage (Vr):40V Average Rectified Current (Io):1A")
      (fields (field (name "Manufacturer") "Hottech(合科泰)"))
      (libsource (lib "easyedapro") (part "1N5819WS"))
    )
    (comp (ref "D253")
      (value "1N5819WS")
      (footprint "easyedapro:SOD-323_L1.8-W1.3-LS2.5-RD")
      (description "Forward Voltage (Vf@If):600mV@1A Reverse Voltage (Vr):40V Average Rectified Current (Io):1A")
      (fields (field (name "Manufacturer") "Hottech(合科泰)"))
      (libsource (lib "easyedapro") (part "1N5819WS"))
    )
    (comp (ref "D254")
      (value "1N5819WS")
      (footprint "easyedapro:SOD-323_L1.8-W1.3-LS2.5-RD")
      (description "Forward Voltage (Vf@If):600mV@1A Reverse Voltage (Vr):40V Average Rectified Current (Io):1A")
      (fields (field (name "Manufacturer") "Hottech(合科泰)"))
      (libsource (lib "easyedapro") (part "1N5819WS"))
    )
    (comp (ref "D255")
      (value "1N5819WS")
      (footprint "easyedapro:SOD-323_L1.8-W1.3-LS2.5-RD")
      (description "Forward Voltage (Vf@If):600mV@1A Reverse Voltage (Vr):40V Average Rectified Current (Io):1A")
      (fields (field (name "Manufacturer") "Hottech(合科泰)"))
      (libsource (lib "easyedapro") (part "1N5819WS"))
    )
    (comp (ref "D256")
      (value "1N5819WS")
      (footprint "easyedapro:SOD-323_L1.8-W1.3-LS2.5-RD")
      (description "Forward Voltage (Vf@If):600mV@1A Reverse Voltage (Vr):40V Average Rectified Current (Io):1A")
      (fields (field (name "Manufacturer") "Hottech(合科泰)"))
      (libsource (lib "easyedapro") (part "1N5819WS"))
    )
    (comp (ref "D257")
      (value "1N5819WS")
      (footprint "easyedapro:SOD-323_L1.8-W1.3-LS2.5-RD")
      (description "Forward Voltage (Vf@If):600mV@1A Reverse Voltage (Vr):40V Average Rectified Current (Io):1A")
      (fields (field (name "Manufacturer") "Hottech(合科泰)"))
      (libsource (lib "easyedapro") (part "1N5819WS"))
    )
    (comp (ref "D258")
      (value "1N5819WS")
      (footprint "easyedapro:SOD-323_L1.8-W1.3-LS2.5-RD")
      (description "Forward Voltage (Vf@If):600mV@1A Reverse Voltage (Vr):40V Average Rectified Current (Io):1A")
      (fields (field (name "Manufacturer") "Hottech(合科泰)"))
      (libsource (lib "easyedapro") (part "1N5819WS"))
    )
    (comp (ref "D259")
      (value "1N5819WS")
      (footprint "easyedapro:SOD-323_L1.8-W1.3-LS2.5-RD")
      (description "Forward Voltage (Vf@If):600mV@1A Reverse Voltage (Vr):40V Average Rectified Current (Io):1A")
      (fields (field (name "Manufacturer") "Hottech(合科泰)"))
      (libsource (lib "easyedapro") (part "1N5819WS"))
    )
    (comp (ref "D260")
      (value "1N5819WS")
      (footprint "easyedapro:SOD-323_L1.8-W1.3-LS2.5-RD")
      (description "Forward Voltage (Vf@If):600mV@1A Reverse Voltage (Vr):40V Average Rectified Current (Io):1A")
      (fields (field (name "Manufacturer") "Hottech(合科泰)"))
      (libsource (lib "easyedapro") (part "1N5819WS"))
    )
    (comp (ref "D261")
      (value "1N5819WS")
      (footprint "easyedapro:SOD-323_L1.8-W1.3-LS2.5-RD")
      (description "Forward Voltage (Vf@If):600mV@1A Reverse Voltage (Vr):40V Average Rectified Current (Io):1A")
      (fields (field (name "Manufacturer") "Hottech(合科泰)"))
      (libsource (lib "easyedapro") (part "1N5819WS"))
    )
    (comp (ref "D262")
      (value "1N5819WS")
      (footprint "easyedapro:SOD-323_L1.8-W1.3-LS2.5-RD")
      (description "Forward Voltage (Vf@If):600mV@1A Reverse Voltage (Vr):40V Average Rectified Current (Io):1A")
      (fields (field (name "Manufacturer") "Hottech(合科泰)"))
      (libsource (lib "easyedapro") (part "1N5819WS"))
    )
    (comp (ref "D263")
      (value "1N5819WS")
      (footprint "easyedapro:SOD-323_L1.8-W1.3-LS2.5-RD")
      (description "Forward Voltage (Vf@If):600mV@1A Reverse Voltage (Vr):40V Average Rectified Current (Io):1A")
      (fields (field (name "Manufacturer") "Hottech(合科泰)"))
      (libsource (lib "easyedapro") (part "1N5819WS"))
    )
    (comp (ref "D264")
      (value "1N5819WS")
      (footprint "easyedapro:SOD-323_L1.8-W1.3-LS2.5-RD")
      (description "Forward Voltage (Vf@If):600mV@1A Reverse Voltage (Vr):40V Average Rectified Current (Io):1A")
      (fields (field (name "Manufacturer") "Hottech(合科泰)"))
      (libsource (lib "easyedapro") (part "1N5819WS"))
    )
    (comp (ref "D265")
      (value "1N5819WS")
      (footprint "easyedapro:SOD-323_L1.8-W1.3-LS2.5-RD")
      (description "Forward Voltage (Vf@If):600mV@1A Reverse Voltage (Vr):40V Average Rectified Current (Io):1A")
      (fields (field (name "Manufacturer") "Hottech(合科泰)"))
      (libsource (lib "easyedapro") (part "1N5819WS"))
    )
    (comp (ref "D266")
      (value "1N5819WS")
      (footprint "easyedapro:SOD-323_L1.8-W1.3-LS2.5-RD")
      (description "Forward Voltage (Vf@If):600mV@1A Reverse Voltage (Vr):40V Average Rectified Current (Io):1A")
      (fields (field (name "Manufacturer") "Hottech(合科泰)"))
      (libsource (lib "easyedapro") (part "1N5819WS"))
    )
    (comp (ref "D267")
      (value "1N5819WS")
      (footprint "easyedapro:SOD-323_L1.8-W1.3-LS2.5-RD")
      (description "Forward Voltage (Vf@If):600mV@1A Reverse Voltage (Vr):40V Average Rectified Current (Io):1A")
      (fields (field (name "Manufacturer") "Hottech(合科泰)"))
      (libsource (lib "easyedapro") (part "1N5819WS"))
    )
    (comp (ref "D268")
      (value "1N5819WS")
      (footprint "easyedapro:SOD-323_L1.8-W1.3-LS2.5-RD")
      (description "Forward Voltage (Vf@If):600mV@1A Reverse Voltage (Vr):40V Average Rectified Current (Io):1A")
      (fields (field (name "Manufacturer") "Hottech(合科泰)"))
      (libsource (lib "easyedapro") (part "1N5819WS"))
    )
    (comp (ref "D269")
      (value "1N5819WS")
      (footprint "easyedapro:SOD-323_L1.8-W1.3-LS2.5-RD")
      (description "Forward Voltage (Vf@If):600mV@1A Reverse Voltage (Vr):40V Average Rectified Current (Io):1A")
      (fields (field (name "Manufacturer") "Hottech(合科泰)"))
      (libsource (lib "easyedapro") (part "1N5819WS"))
    )
    (comp (ref "D270")
      (value "1N5819WS")
      (footprint "easyedapro:SOD-323_L1.8-W1.3-LS2.5-RD")
      (description "Forward Voltage (Vf@If):600mV@1A Reverse Voltage (Vr):40V Average Rectified Current (Io):1A")
      (fields (field (name "Manufacturer") "Hottech(合科泰)"))
      (libsource (lib "easyedapro") (part "1N5819WS"))
    )
    (comp (ref "D271")
      (value "1N5819WS")
      (footprint "easyedapro:SOD-323_L1.8-W1.3-LS2.5-RD")
      (description "Forward Voltage (Vf@If):600mV@1A Reverse Voltage (Vr):40V Average Rectified Current (Io):1A")
      (fields (field (name "Manufacturer") "Hottech(合科泰)"))
      (libsource (lib "easyedapro") (part "1N5819WS"))
    )
    (comp (ref "D272")
      (value "1N5819WS")
      (footprint "easyedapro:SOD-323_L1.8-W1.3-LS2.5-RD")
      (description "Forward Voltage (Vf@If):600mV@1A Reverse Voltage (Vr):40V Average Rectified Current (Io):1A")
      (fields (field (name "Manufacturer") "Hottech(合科泰)"))
      (libsource (lib "easyedapro") (part "1N5819WS"))
    )
    (comp (ref "D273")
      (value "1N5819WS")
      (footprint "easyedapro:SOD-323_L1.8-W1.3-LS2.5-RD")
      (description "Forward Voltage (Vf@If):600mV@1A Reverse Voltage (Vr):40V Average Rectified Current (Io):1A")
      (fields (field (name "Manufacturer") "Hottech(合科泰)"))
      (libsource (lib "easyedapro") (part "1N5819WS"))
    )
    (comp (ref "D274")
      (value "1N5819WS")
      (footprint "easyedapro:SOD-323_L1.8-W1.3-LS2.5-RD")
      (description "Forward Voltage (Vf@If):600mV@1A Reverse Voltage (Vr):40V Average Rectified Current (Io):1A")
      (fields (field (name "Manufacturer") "Hottech(合科泰)"))
      (libsource (lib "easyedapro") (part "1N5819WS"))
    )
    (comp (ref "D275")
      (value "1N5819WS")
      (footprint "easyedapro:SOD-323_L1.8-W1.3-LS2.5-RD")
      (description "Forward Voltage (Vf@If):600mV@1A Reverse Voltage (Vr):40V Average Rectified Current (Io):1A")
      (fields (field (name "Manufacturer") "Hottech(合科泰)"))
      (libsource (lib "easyedapro") (part "1N5819WS"))
    )
    (comp (ref "D276")
      (value "1N5819WS")
      (footprint "easyedapro:SOD-323_L1.8-W1.3-LS2.5-RD")
      (description "Forward Voltage (Vf@If):600mV@1A Reverse Voltage (Vr):40V Average Rectified Current (Io):1A")
      (fields (field (name "Manufacturer") "Hottech(合科泰)"))
      (libsource (lib "easyedapro") (part "1N5819WS"))
    )
    (comp (ref "D277")
      (value "1N5819WS")
      (footprint "easyedapro:SOD-323_L1.8-W1.3-LS2.5-RD")
      (description "Forward Voltage (Vf@If):600mV@1A Reverse Voltage (Vr):40V Average Rectified Current (Io):1A")
      (fields (field (name "Manufacturer") "Hottech(合科泰)"))
      (libsource (lib "easyedapro") (part "1N5819WS"))
    )
    (comp (ref "D278")
      (value "1N5819WS")
      (footprint "easyedapro:SOD-323_L1.8-W1.3-LS2.5-RD")
      (description "Forward Voltage (Vf@If):600mV@1A Reverse Voltage (Vr):40V Average Rectified Current (Io):1A")
      (fields (field (name "Manufacturer") "Hottech(合科泰)"))
      (libsource (lib "easyedapro") (part "1N5819WS"))
    )
    (comp (ref "D279")
      (value "1N5819WS")
      (footprint "easyedapro:SOD-323_L1.8-W1.3-LS2.5-RD")
      (description "Forward Voltage (Vf@If):600mV@1A Reverse Voltage (Vr):40V Average Rectified Current (Io):1A")
      (fields (field (name "Manufacturer") "Hottech(合科泰)"))
      (libsource (lib "easyedapro") (part "1N5819WS"))
    )
    (comp (ref "D280")
      (value "1N5819WS")
      (footprint "easyedapro:SOD-323_L1.8-W1.3-LS2.5-RD")
      (description "Forward Voltage (Vf@If):600mV@1A Reverse Voltage (Vr):40V Average Rectified Current (Io):1A")
      (fields (field (name "Manufacturer") "Hottech(合科泰)"))
      (libsource (lib "easyedapro") (part "1N5819WS"))
    )
    (comp (ref "D281")
      (value "1N5819WS")
      (footprint "easyedapro:SOD-323_L1.8-W1.3-LS2.5-RD")
      (description "Forward Voltage (Vf@If):600mV@1A Reverse Voltage (Vr):40V Average Rectified Current (Io):1A")
      (fields (field (name "Manufacturer") "Hottech(合科泰)"))
      (libsource (lib "easyedapro") (part "1N5819WS"))
    )
    (comp (ref "D282")
      (value "1N5819WS")
      (footprint "easyedapro:SOD-323_L1.8-W1.3-LS2.5-RD")
      (description "Forward Voltage (Vf@If):600mV@1A Reverse Voltage (Vr):40V Average Rectified Current (Io):1A")
      (fields (field (name "Manufacturer") "Hottech(合科泰)"))
      (libsource (lib "easyedapro") (part "1N5819WS"))
    )
    (comp (ref "D283")
      (value "1N5819WS")
      (footprint "easyedapro:SOD-323_L1.8-W1.3-LS2.5-RD")
      (description "Forward Voltage (Vf@If):600mV@1A Reverse Voltage (Vr):40V Average Rectified Current (Io):1A")
      (fields (field (name "Manufacturer") "Hottech(合科泰)"))
      (libsource (lib "easyedapro") (part "1N5819WS"))
    )
    (comp (ref "D284")
      (value "1N5819WS")
      (footprint "easyedapro:SOD-323_L1.8-W1.3-LS2.5-RD")
      (description "Forward Voltage (Vf@If):600mV@1A Reverse Voltage (Vr):40V Average Rectified Current (Io):1A")
      (fields (field (name "Manufacturer") "Hottech(合科泰)"))
      (libsource (lib "easyedapro") (part "1N5819WS"))
    )
    (comp (ref "D285")
      (value "1N5819WS")
      (footprint "easyedapro:SOD-323_L1.8-W1.3-LS2.5-RD")
      (description "Forward Voltage (Vf@If):600mV@1A Reverse Voltage (Vr):40V Average Rectified Current (Io):1A")
      (fields (field (name "Manufacturer") "Hottech(合科泰)"))
      (libsource (lib "easyedapro") (part "1N5819WS"))
    )
    (comp (ref "D286")
      (value "1N5819WS")
      (footprint "easyedapro:SOD-323_L1.8-W1.3-LS2.5-RD")
      (description "Forward Voltage (Vf@If):600mV@1A Reverse Voltage (Vr):40V Average Rectified Current (Io):1A")
      (fields (field (name "Manufacturer") "Hottech(合科泰)"))
      (libsource (lib "easyedapro") (part "1N5819WS"))
    )
    (comp (ref "D287")
      (value "1N5819WS")
      (footprint "easyedapro:SOD-323_L1.8-W1.3-LS2.5-RD")
      (description "Forward Voltage (Vf@If):600mV@1A Reverse Voltage (Vr):40V Average Rectified Current (Io):1A")
      (fields (field (name "Manufacturer") "Hottech(合科泰)"))
      (libsource (lib "easyedapro") (part "1N5819WS"))
    )
    (comp (ref "D288")
      (value "1N5819WS")
      (footprint "easyedapro:SOD-323_L1.8-W1.3-LS2.5-RD")
      (description "Forward Voltage (Vf@If):600mV@1A Reverse Voltage (Vr):40V Average Rectified Current (Io):1A")
      (fields (field (name "Manufacturer") "Hottech(合科泰)"))
      (libsource (lib "easyedapro") (part "1N5819WS"))
    )
    (comp (ref "D289")
      (value "1N5819WS")
      (footprint "easyedapro:SOD-323_L1.8-W1.3-LS2.5-RD")
      (description "Forward Voltage (Vf@If):600mV@1A Reverse Voltage (Vr):40V Average Rectified Current (Io):1A")
      (fields (field (name "Manufacturer") "Hottech(合科泰)"))
      (libsource (lib "easyedapro") (part "1N5819WS"))
    )
    (comp (ref "D290")
      (value "1N5819WS")
      (footprint "easyedapro:SOD-323_L1.8-W1.3-LS2.5-RD")
      (description "Forward Voltage (Vf@If):600mV@1A Reverse Voltage (Vr):40V Average Rectified Current (Io):1A")
      (fields (field (name "Manufacturer") "Hottech(合科泰)"))
      (libsource (lib "easyedapro") (part "1N5819WS"))
    )
    (comp (ref "ENC201")
      (value "PEC12R-4120F-S0012")
      (footprint "easyedapro:SW-TH_PEC12R-4120F-S0012_1")
      (fields (field (name "Manufacturer") "BOURNS"))
      (libsource (lib "easyedapro") (part "PEC12R-4120F-S0012_RF_v1.0"))
    )
    (comp (ref "FPC1")
      (value "FH28-10S-0.5SH(05)")
      (footprint "easyedapro:FFC-SMD_10P-P0.50_FH28-10S-0.5SH-05")
      (fields (field (name "Manufacturer") "HRS(广濑)"))
      (libsource (lib "easyedapro") (part "FH28-10S-0.5SH(05)"))
    )
    (comp (ref "J201")
      (value "CPG151101S11-16")
      (footprint "easyedapro:SMD_KEYBOARD-SW_1")
      (fields (field (name "Manufacturer") "Kailh(凯华)"))
      (libsource (lib "easyedapro") (part "CPG151101S11-16_RF_v1.0"))
    )
    (comp (ref "J202")
      (value "CPG151101S11-16")
      (footprint "easyedapro:SMD_KEYBOARD-SW_1")
      (fields (field (name "Manufacturer") "Kailh(凯华)"))
      (libsource (lib "easyedapro") (part "CPG151101S11-16_RF_v1.0"))
    )
    (comp (ref "J203")
      (value "CPG151101S11-16")
      (footprint "easyedapro:SMD_KEYBOARD-SW_1")
      (fields (field (name "Manufacturer") "Kailh(凯华)"))
      (libsource (lib "easyedapro") (part "CPG151101S11-16_RF_v1.0"))
    )
    (comp (ref "J204")
      (value "CPG151101S11-16")
      (footprint "easyedapro:SMD_KEYBOARD-SW_1")
      (fields (field (name "Manufacturer") "Kailh(凯华)"))
      (libsource (lib "easyedapro") (part "CPG151101S11-16_RF_v1.0"))
    )
    (comp (ref "J205")
      (value "CPG151101S11-16")
      (footprint "easyedapro:SMD_KEYBOARD-SW_1")
      (fields (field (name "Manufacturer") "Kailh(凯华)"))
      (libsource (lib "easyedapro") (part "CPG151101S11-16_RF_v1.0"))
    )
    (comp (ref "J206")
      (value "CPG151101S11-16")
      (footprint "easyedapro:SMD_KEYBOARD-SW_1")
      (fields (field (name "Manufacturer") "Kailh(凯华)"))
      (libsource (lib "easyedapro") (part "CPG151101S11-16_RF_v1.0"))
    )
    (comp (ref "J207")
      (value "CPG151101S11-16")
      (footprint "easyedapro:SMD_KEYBOARD-SW_1")
      (fields (field (name "Manufacturer") "Kailh(凯华)"))
      (libsource (lib "easyedapro") (part "CPG151101S11-16_RF_v1.0"))
    )
    (comp (ref "J208")
      (value "CPG151101S11-16")
      (footprint "easyedapro:SMD_KEYBOARD-SW_1")
      (fields (field (name "Manufacturer") "Kailh(凯华)"))
      (libsource (lib "easyedapro") (part "CPG151101S11-16_RF_v1.0"))
    )
    (comp (ref "J209")
      (value "CPG151101S11-16")
      (footprint "easyedapro:SMD_KEYBOARD-SW_1")
      (fields (field (name "Manufacturer") "Kailh(凯华)"))
      (libsource (lib "easyedapro") (part "CPG151101S11-16_RF_v1.0"))
    )
    (comp (ref "J210")
      (value "CPG151101S11-16")
      (footprint "easyedapro:SMD_KEYBOARD-SW_1")
      (fields (field (name "Manufacturer") "Kailh(凯华)"))
      (libsource (lib "easyedapro") (part "CPG151101S11-16_RF_v1.0"))
    )
    (comp (ref "J211")
      (value "CPG151101S11-16")
      (footprint "easyedapro:SMD_KEYBOARD-SW_1")
      (fields (field (name "Manufacturer") "Kailh(凯华)"))
      (libsource (lib "easyedapro") (part "CPG151101S11-16_RF_v1.0"))
    )
    (comp (ref "J212")
      (value "CPG151101S11-16")
      (footprint "easyedapro:SMD_KEYBOARD-SW_1")
      (fields (field (name "Manufacturer") "Kailh(凯华)"))
      (libsource (lib "easyedapro") (part "CPG151101S11-16_RF_v1.0"))
    )
    (comp (ref "J213")
      (value "CPG151101S11-16")
      (footprint "easyedapro:SMD_KEYBOARD-SW_1")
      (fields (field (name "Manufacturer") "Kailh(凯华)"))
      (libsource (lib "easyedapro") (part "CPG151101S11-16_RF_v1.0"))
    )
    (comp (ref "J214")
      (value "CPG151101S11-16")
      (footprint "easyedapro:SMD_KEYBOARD-SW_1")
      (fields (field (name "Manufacturer") "Kailh(凯华)"))
      (libsource (lib "easyedapro") (part "CPG151101S11-16_RF_v1.0"))
    )
    (comp (ref "J215")
      (value "CPG151101S11-16")
      (footprint "easyedapro:SMD_KEYBOARD-SW_1")
      (fields (field (name "Manufacturer") "Kailh(凯华)"))
      (libsource (lib "easyedapro") (part "CPG151101S11-16_RF_v1.0"))
    )
    (comp (ref "J216")
      (value "CPG151101S11-16")
      (footprint "easyedapro:SMD_KEYBOARD-SW_1")
      (fields (field (name "Manufacturer") "Kailh(凯华)"))
      (libsource (lib "easyedapro") (part "CPG151101S11-16_RF_v1.0"))
    )
    (comp (ref "J217")
      (value "CPG151101S11-16")
      (footprint "easyedapro:SMD_KEYBOARD-SW_1")
      (fields (field (name "Manufacturer") "Kailh(凯华)"))
      (libsource (lib "easyedapro") (part "CPG151101S11-16_RF_v1.0"))
    )
    (comp (ref "J218")
      (value "CPG151101S11-16")
      (footprint "easyedapro:SMD_KEYBOARD-SW_1")
      (fields (field (name "Manufacturer") "Kailh(凯华)"))
      (libsource (lib "easyedapro") (part "CPG151101S11-16_RF_v1.0"))
    )
    (comp (ref "J219")
      (value "CPG151101S11-16")
      (footprint "easyedapro:SMD_KEYBOARD-SW_1")
      (fields (field (name "Manufacturer") "Kailh(凯华)"))
      (libsource (lib "easyedapro") (part "CPG151101S11-16_RF_v1.0"))
    )
    (comp (ref "J220")
      (value "CPG151101S11-16")
      (footprint "easyedapro:SMD_KEYBOARD-SW_1")
      (fields (field (name "Manufacturer") "Kailh(凯华)"))
      (libsource (lib "easyedapro") (part "CPG151101S11-16_RF_v1.0"))
    )
    (comp (ref "J221")
      (value "CPG151101S11-16")
      (footprint "easyedapro:SMD_KEYBOARD-SW_1")
      (fields (field (name "Manufacturer") "Kailh(凯华)"))
      (libsource (lib "easyedapro") (part "CPG151101S11-16_RF_v1.0"))
    )
    (comp (ref "J222")
      (value "CPG151101S11-16")
      (footprint "easyedapro:SMD_KEYBOARD-SW_1")
      (fields (field (name "Manufacturer") "Kailh(凯华)"))
      (libsource (lib "easyedapro") (part "CPG151101S11-16_RF_v1.0"))
    )
    (comp (ref "J223")
      (value "CPG151101S11-16")
      (footprint "easyedapro:SMD_KEYBOARD-SW_1")
      (fields (field (name "Manufacturer") "Kailh(凯华)"))
      (libsource (lib "easyedapro") (part "CPG151101S11-16_RF_v1.0"))
    )
    (comp (ref "J224")
      (value "CPG151101S11-16")
      (footprint "easyedapro:SMD_KEYBOARD-SW_1")
      (fields (field (name "Manufacturer") "Kailh(凯华)"))
      (libsource (lib "easyedapro") (part "CPG151101S11-16_RF_v1.0"))
    )
    (comp (ref "J225")
      (value "CPG151101S11-16")
      (footprint "easyedapro:SMD_KEYBOARD-SW_1")
      (fields (field (name "Manufacturer") "Kailh(凯华)"))
      (libsource (lib "easyedapro") (part "CPG151101S11-16_RF_v1.0"))
    )
    (comp (ref "J226")
      (value "CPG151101S11-16")
      (footprint "easyedapro:SMD_KEYBOARD-SW_1")
      (fields (field (name "Manufacturer") "Kailh(凯华)"))
      (libsource (lib "easyedapro") (part "CPG151101S11-16_RF_v1.0"))
    )
    (comp (ref "J227")
      (value "CPG151101S11-16")
      (footprint "easyedapro:SMD_KEYBOARD-SW_1")
      (fields (field (name "Manufacturer") "Kailh(凯华)"))
      (libsource (lib "easyedapro") (part "CPG151101S11-16_RF_v1.0"))
    )
    (comp (ref "J228")
      (value "CPG151101S11-16")
      (footprint "easyedapro:SMD_KEYBOARD-SW_1")
      (fields (field (name "Manufacturer") "Kailh(凯华)"))
      (libsource (lib "easyedapro") (part "CPG151101S11-16_RF_v1.0"))
    )
    (comp (ref "J229")
      (value "CPG151101S11-16")
      (footprint "easyedapro:SMD_KEYBOARD-SW_1")
      (fields (field (name "Manufacturer") "Kailh(凯华)"))
      (libsource (lib "easyedapro") (part "CPG151101S11-16_RF_v1.0"))
    )
    (comp (ref "J230")
      (value "CPG151101S11-16")
      (footprint "easyedapro:SMD_KEYBOARD-SW_1")
      (fields (field (name "Manufacturer") "Kailh(凯华)"))
      (libsource (lib "easyedapro") (part "CPG151101S11-16_RF_v1.0"))
    )
    (comp (ref "J231")
      (value "CPG151101S11-16")
      (footprint "easyedapro:SMD_KEYBOARD-SW_1")
      (fields (field (name "Manufacturer") "Kailh(凯华)"))
      (libsource (lib "easyedapro") (part "CPG151101S11-16_RF_v1.0"))
    )
    (comp (ref "J232")
      (value "CPG151101S11-16")
      (footprint "easyedapro:SMD_KEYBOARD-SW_1")
      (fields (field (name "Manufacturer") "Kailh(凯华)"))
      (libsource (lib "easyedapro") (part "CPG151101S11-16_RF_v1.0"))
    )
    (comp (ref "J233")
      (value "CPG151101S11-16")
      (footprint "easyedapro:SMD_KEYBOARD-SW_1")
      (fields (field (name "Manufacturer") "Kailh(凯华)"))
      (libsource (lib "easyedapro") (part "CPG151101S11-16_RF_v1.0"))
    )
    (comp (ref "J234")
      (value "CPG151101S11-16")
      (footprint "easyedapro:SMD_KEYBOARD-SW_1")
      (fields (field (name "Manufacturer") "Kailh(凯华)"))
      (libsource (lib "easyedapro") (part "CPG151101S11-16_RF_v1.0"))
    )
    (comp (ref "J235")
      (value "CPG151101S11-16")
      (footprint "easyedapro:SMD_KEYBOARD-SW_1")
      (fields (field (name "Manufacturer") "Kailh(凯华)"))
      (libsource (lib "easyedapro") (part "CPG151101S11-16_RF_v1.0"))
    )
    (comp (ref "J236")
      (value "CPG151101S11-16")
      (footprint "easyedapro:SMD_KEYBOARD-SW_1")
      (fields (field (name "Manufacturer") "Kailh(凯华)"))
      (libsource (lib "easyedapro") (part "CPG151101S11-16_RF_v1.0"))
    )
    (comp (ref "J237")
      (value "CPG151101S11-16")
      (footprint "easyedapro:SMD_KEYBOARD-SW_1")
      (fields (field (name "Manufacturer") "Kailh(凯华)"))
      (libsource (lib "easyedapro") (part "CPG151101S11-16_RF_v1.0"))
    )
    (comp (ref "J238")
      (value "CPG151101S11-16")
      (footprint "easyedapro:SMD_KEYBOARD-SW_1")
      (fields (field (name "Manufacturer") "Kailh(凯华)"))
      (libsource (lib "easyedapro") (part "CPG151101S11-16_RF_v1.0"))
    )
    (comp (ref "J239")
      (value "CPG151101S11-16")
      (footprint "easyedapro:SMD_KEYBOARD-SW_1")
      (fields (field (name "Manufacturer") "Kailh(凯华)"))
      (libsource (lib "easyedapro") (part "CPG151101S11-16_RF_v1.0"))
    )
    (comp (ref "J240")
      (value "CPG151101S11-16")
      (footprint "easyedapro:SMD_KEYBOARD-SW_1")
      (fields (field (name "Manufacturer") "Kailh(凯华)"))
      (libsource (lib "easyedapro") (part "CPG151101S11-16_RF_v1.0"))
    )
    (comp (ref "J241")
      (value "CPG151101S11-16")
      (footprint "easyedapro:SMD_KEYBOARD-SW_1")
      (fields (field (name "Manufacturer") "Kailh(凯华)"))
      (libsource (lib "easyedapro") (part "CPG151101S11-16_RF_v1.0"))
    )
    (comp (ref "J242")
      (value "CPG151101S11-16")
      (footprint "easyedapro:SMD_KEYBOARD-SW_1")
      (fields (field (name "Manufacturer") "Kailh(凯华)"))
      (libsource (lib "easyedapro") (part "CPG151101S11-16_RF_v1.0"))
    )
    (comp (ref "J243")
      (value "CPG151101S11-16")
      (footprint "easyedapro:SMD_KEYBOARD-SW_1")
      (fields (field (name "Manufacturer") "Kailh(凯华)"))
      (libsource (lib "easyedapro") (part "CPG151101S11-16_RF_v1.0"))
    )
    (comp (ref "J244")
      (value "CPG151101S11-16")
      (footprint "easyedapro:SMD_KEYBOARD-SW_1")
      (fields (field (name "Manufacturer") "Kailh(凯华)"))
      (libsource (lib "easyedapro") (part "CPG151101S11-16_RF_v1.0"))
    )
    (comp (ref "J245")
      (value "CPG151101S11-16")
      (footprint "easyedapro:SMD_KEYBOARD-SW_1")
      (fields (field (name "Manufacturer") "Kailh(凯华)"))
      (libsource (lib "easyedapro") (part "CPG151101S11-16_RF_v1.0"))
    )
    (comp (ref "J246")
      (value "CPG151101S11-16")
      (footprint "easyedapro:SMD_KEYBOARD-SW_1")
      (fields (field (name "Manufacturer") "Kailh(凯华)"))
      (libsource (lib "easyedapro") (part "CPG151101S11-16_RF_v1.0"))
    )
    (comp (ref "J247")
      (value "CPG151101S11-16")
      (footprint "easyedapro:SMD_KEYBOARD-SW_1")
      (fields (field (name "Manufacturer") "Kailh(凯华)"))
      (libsource (lib "easyedapro") (part "CPG151101S11-16_RF_v1.0"))
    )
    (comp (ref "J248")
      (value "CPG151101S11-16")
      (footprint "easyedapro:SMD_KEYBOARD-SW_1")
      (fields (field (name "Manufacturer") "Kailh(凯华)"))
      (libsource (lib "easyedapro") (part "CPG151101S11-16_RF_v1.0"))
    )
    (comp (ref "J249")
      (value "CPG151101S11-16")
      (footprint "easyedapro:SMD_KEYBOARD-SW_1")
      (fields (field (name "Manufacturer") "Kailh(凯华)"))
      (libsource (lib "easyedapro") (part "CPG151101S11-16_RF_v1.0"))
    )
    (comp (ref "J250")
      (value "CPG151101S11-16")
      (footprint "easyedapro:SMD_KEYBOARD-SW_1")
      (fields (field (name "Manufacturer") "Kailh(凯华)"))
      (libsource (lib "easyedapro") (part "CPG151101S11-16_RF_v1.0"))
    )
    (comp (ref "J251")
      (value "CPG151101S11-16")
      (footprint "easyedapro:SMD_KEYBOARD-SW_1")
      (fields (field (name "Manufacturer") "Kailh(凯华)"))
      (libsource (lib "easyedapro") (part "CPG151101S11-16_RF_v1.0"))
    )
    (comp (ref "J252")
      (value "CPG151101S11-16")
      (footprint "easyedapro:SMD_KEYBOARD-SW_1")
      (fields (field (name "Manufacturer") "Kailh(凯华)"))
      (libsource (lib "easyedapro") (part "CPG151101S11-16_RF_v1.0"))
    )
    (comp (ref "J253")
      (value "CPG151101S11-16")
      (footprint "easyedapro:SMD_KEYBOARD-SW_1")
      (fields (field (name "Manufacturer") "Kailh(凯华)"))
      (libsource (lib "easyedapro") (part "CPG151101S11-16_RF_v1.0"))
    )
    (comp (ref "J254")
      (value "CPG151101S11-16")
      (footprint "easyedapro:SMD_KEYBOARD-SW_1")
      (fields (field (name "Manufacturer") "Kailh(凯华)"))
      (libsource (lib "easyedapro") (part "CPG151101S11-16_RF_v1.0"))
    )
    (comp (ref "J255")
      (value "CPG151101S11-16")
      (footprint "easyedapro:SMD_KEYBOARD-SW_1")
      (fields (field (name "Manufacturer") "Kailh(凯华)"))
      (libsource (lib "easyedapro") (part "CPG151101S11-16_RF_v1.0"))
    )
    (comp (ref "J256")
      (value "CPG151101S11-16")
      (footprint "easyedapro:SMD_KEYBOARD-SW_1")
      (fields (field (name "Manufacturer") "Kailh(凯华)"))
      (libsource (lib "easyedapro") (part "CPG151101S11-16_RF_v1.0"))
    )
    (comp (ref "J257")
      (value "CPG151101S11-16")
      (footprint "easyedapro:SMD_KEYBOARD-SW_1")
      (fields (field (name "Manufacturer") "Kailh(凯华)"))
      (libsource (lib "easyedapro") (part "CPG151101S11-16_RF_v1.0"))
    )
    (comp (ref "J258")
      (value "CPG151101S11-16")
      (footprint "easyedapro:SMD_KEYBOARD-SW_1")
      (fields (field (name "Manufacturer") "Kailh(凯华)"))
      (libsource (lib "easyedapro") (part "CPG151101S11-16_RF_v1.0"))
    )
    (comp (ref "J259")
      (value "CPG151101S11-16")
      (footprint "easyedapro:SMD_KEYBOARD-SW_1")
      (fields (field (name "Manufacturer") "Kailh(凯华)"))
      (libsource (lib "easyedapro") (part "CPG151101S11-16_RF_v1.0"))
    )
    (comp (ref "J260")
      (value "CPG151101S11-16")
      (footprint "easyedapro:SMD_KEYBOARD-SW_1")
      (fields (field (name "Manufacturer") "Kailh(凯华)"))
      (libsource (lib "easyedapro") (part "CPG151101S11-16_RF_v1.0"))
    )
    (comp (ref "J261")
      (value "CPG151101S11-16")
      (footprint "easyedapro:SMD_KEYBOARD-SW_1")
      (fields (field (name "Manufacturer") "Kailh(凯华)"))
      (libsource (lib "easyedapro") (part "CPG151101S11-16_RF_v1.0"))
    )
    (comp (ref "J262")
      (value "CPG151101S11-16")
      (footprint "easyedapro:SMD_KEYBOARD-SW_1")
      (fields (field (name "Manufacturer") "Kailh(凯华)"))
      (libsource (lib "easyedapro") (part "CPG151101S11-16_RF_v1.0"))
    )
    (comp (ref "J263")
      (value "CPG151101S11-16")
      (footprint "easyedapro:SMD_KEYBOARD-SW_1")
      (fields (field (name "Manufacturer") "Kailh(凯华)"))
      (libsource (lib "easyedapro") (part "CPG151101S11-16_RF_v1.0"))
    )
    (comp (ref "J264")
      (value "CPG151101S11-16")
      (footprint "easyedapro:SMD_KEYBOARD-SW_1")
      (fields (field (name "Manufacturer") "Kailh(凯华)"))
      (libsource (lib "easyedapro") (part "CPG151101S11-16_RF_v1.0"))
    )
    (comp (ref "J265")
      (value "CPG151101S11-16")
      (footprint "easyedapro:SMD_KEYBOARD-SW_1")
      (fields (field (name "Manufacturer") "Kailh(凯华)"))
      (libsource (lib "easyedapro") (part "CPG151101S11-16_RF_v1.0"))
    )
    (comp (ref "J266")
      (value "CPG151101S11-16")
      (footprint "easyedapro:SMD_KEYBOARD-SW_1")
      (fields (field (name "Manufacturer") "Kailh(凯华)"))
      (libsource (lib "easyedapro") (part "CPG151101S11-16_RF_v1.0"))
    )
    (comp (ref "J267")
      (value "CPG151101S11-16")
      (footprint "easyedapro:SMD_KEYBOARD-SW_1")
      (fields (field (name "Manufacturer") "Kailh(凯华)"))
      (libsource (lib "easyedapro") (part "CPG151101S11-16_RF_v1.0"))
    )
    (comp (ref "J268")
      (value "CPG151101S11-16")
      (footprint "easyedapro:SMD_KEYBOARD-SW_1")
      (fields (field (name "Manufacturer") "Kailh(凯华)"))
      (libsource (lib "easyedapro") (part "CPG151101S11-16_RF_v1.0"))
    )
    (comp (ref "J269")
      (value "CPG151101S11-16")
      (footprint "easyedapro:SMD_KEYBOARD-SW_1")
      (fields (field (name "Manufacturer") "Kailh(凯华)"))
      (libsource (lib "easyedapro") (part "CPG151101S11-16_RF_v1.0"))
    )
    (comp (ref "J270")
      (value "CPG151101S11-16")
      (footprint "easyedapro:SMD_KEYBOARD-SW_1")
      (fields (field (name "Manufacturer") "Kailh(凯华)"))
      (libsource (lib "easyedapro") (part "CPG151101S11-16_RF_v1.0"))
    )
    (comp (ref "J271")
      (value "CPG151101S11-16")
      (footprint "easyedapro:SMD_KEYBOARD-SW_1")
      (fields (field (name "Manufacturer") "Kailh(凯华)"))
      (libsource (lib "easyedapro") (part "CPG151101S11-16_RF_v1.0"))
    )
    (comp (ref "J272")
      (value "CPG151101S11-16")
      (footprint "easyedapro:SMD_KEYBOARD-SW_1")
      (fields (field (name "Manufacturer") "Kailh(凯华)"))
      (libsource (lib "easyedapro") (part "CPG151101S11-16_RF_v1.0"))
    )
    (comp (ref "J273")
      (value "CPG151101S11-16")
      (footprint "easyedapro:SMD_KEYBOARD-SW_1")
      (fields (field (name "Manufacturer") "Kailh(凯华)"))
      (libsource (lib "easyedapro") (part "CPG151101S11-16_RF_v1.0"))
    )
    (comp (ref "J274")
      (value "CPG151101S11-16")
      (footprint "easyedapro:SMD_KEYBOARD-SW_1")
      (fields (field (name "Manufacturer") "Kailh(凯华)"))
      (libsource (lib "easyedapro") (part "CPG151101S11-16_RF_v1.0"))
    )
    (comp (ref "J275")
      (value "CPG151101S11-16")
      (footprint "easyedapro:SMD_KEYBOARD-SW_1")
      (fields (field (name "Manufacturer") "Kailh(凯华)"))
      (libsource (lib "easyedapro") (part "CPG151101S11-16_RF_v1.0"))
    )
    (comp (ref "J276")
      (value "CPG151101S11-16")
      (footprint "easyedapro:SMD_KEYBOARD-SW_1")
      (fields (field (name "Manufacturer") "Kailh(凯华)"))
      (libsource (lib "easyedapro") (part "CPG151101S11-16_RF_v1.0"))
    )
    (comp (ref "J277")
      (value "CPG151101S11-16")
      (footprint "easyedapro:SMD_KEYBOARD-SW_1")
      (fields (field (name "Manufacturer") "Kailh(凯华)"))
      (libsource (lib "easyedapro") (part "CPG151101S11-16_RF_v1.0"))
    )
    (comp (ref "J278")
      (value "CPG151101S11-16")
      (footprint "easyedapro:SMD_KEYBOARD-SW_1")
      (fields (field (name "Manufacturer") "Kailh(凯华)"))
      (libsource (lib "easyedapro") (part "CPG151101S11-16_RF_v1.0"))
    )
    (comp (ref "MH201")
      (value "STANDOFF_M2.5x3.5MM")
      (footprint "easyedapro:STANDOFF_M2.5x3.5MM_RF_v1.0")
      (description "Standoff, Steel, M2.5, Hex Female-Female, 3.5 mm, 4.9 mm, WA-SMSI Series")
      (fields (field (name "Manufacturer") "WURTH ELEKTRONIK"))
      (libsource (lib "easyedapro") (part "9774035151R_RF_v1.0"))
    )
    (comp (ref "MH202")
      (value "STANDOFF_M2.5x3.5MM")
      (footprint "easyedapro:STANDOFF_M2.5x3.5MM_RF_v1.0")
      (description "Standoff, Steel, M2.5, Hex Female-Female, 3.5 mm, 4.9 mm, WA-SMSI Series")
      (fields (field (name "Manufacturer") "WURTH ELEKTRONIK"))
      (libsource (lib "easyedapro") (part "9774035151R_RF_v1.0"))
    )
    (comp (ref "MH203")
      (value "STANDOFF_M2.5x3.5MM")
      (footprint "easyedapro:STANDOFF_M2.5x3.5MM_RF_v1.0")
      (description "Standoff, Steel, M2.5, Hex Female-Female, 3.5 mm, 4.9 mm, WA-SMSI Series")
      (fields (field (name "Manufacturer") "WURTH ELEKTRONIK"))
      (libsource (lib "easyedapro") (part "9774035151R_RF_v1.0"))
    )
    (comp (ref "MH204")
      (value "STANDOFF_M2.5x3.5MM")
      (footprint "easyedapro:STANDOFF_M2.5x3.5MM_RF_v1.0")
      (description "Standoff, Steel, M2.5, Hex Female-Female, 3.5 mm, 4.9 mm, WA-SMSI Series")
      (fields (field (name "Manufacturer") "WURTH ELEKTRONIK"))
      (libsource (lib "easyedapro") (part "9774035151R_RF_v1.0"))
    )
    (comp (ref "MH205")
      (value "~")
      (footprint "easyedapro:MH_7.5X3.2MM_RF_v1.0")
      (libsource (lib "easyedapro") (part "MH_7.5X3.2MM_RF_v1.0"))
    )
    (comp (ref "MH206")
      (value "~")
      (footprint "easyedapro:MH_7.5X3.2MM_RF_v1.0")
      (libsource (lib "easyedapro") (part "MH_7.5X3.2MM_RF_v1.0"))
    )
    (comp (ref "MH207")
      (value "~")
      (footprint "easyedapro:MH_7.5X3.2MM_RF_v1.0")
      (libsource (lib "easyedapro") (part "MH_7.5X3.2MM_RF_v1.0"))
    )
    (comp (ref "MH208")
      (value "~")
      (footprint "easyedapro:MH_7.5X3.2MM_RF_v1.0")
      (libsource (lib "easyedapro") (part "MH_7.5X3.2MM_RF_v1.0"))
    )
    (comp (ref "R201")
      (value "10kΩ")
      (footprint "easyedapro:R0402")
      (fields
        (field (name "Manufacturer Part") "0402WGF1002TCE")
        (field (name "Manufacturer") "UNI-ROYAL(厚声)")
      )
      (libsource (lib "easyedapro") (part "0402WGF1002TCE"))
    )
    (comp (ref "R202")
      (value "10kΩ")
      (footprint "easyedapro:R0402")
      (fields
        (field (name "Manufacturer Part") "0402WGF1002TCE")
        (field (name "Manufacturer") "UNI-ROYAL(厚声)")
      )
      (libsource (lib "easyedapro") (part "0402WGF1002TCE"))
    )
    (comp (ref "R205")
      (value "10kΩ")
      (footprint "easyedapro:R0402")
      (fields
        (field (name "Manufacturer Part") "0402WGF1002TCE")
        (field (name "Manufacturer") "UNI-ROYAL(厚声)")
      )
      (libsource (lib "easyedapro") (part "0402WGF1002TCE"))
    )
    (comp (ref "R207")
      (value "10kΩ")
      (footprint "easyedapro:R0402")
      (fields
        (field (name "Manufacturer Part") "0402WGF1002TCE")
        (field (name "Manufacturer") "UNI-ROYAL(厚声)")
      )
      (libsource (lib "easyedapro") (part "0402WGF1002TCE"))
    )
    (comp (ref "R223")
      (value "10kΩ")
      (footprint "easyedapro:R0402")
      (fields
        (field (name "Manufacturer Part") "0402WGF1002TCE")
        (field (name "Manufacturer") "UNI-ROYAL(厚声)")
      )
      (libsource (lib "easyedapro") (part "0402WGF1002TCE"))
    )
    (comp (ref "R224")
      (value "10kΩ")
      (footprint "easyedapro:R0402")
      (fields
        (field (name "Manufacturer Part") "0402WGF1002TCE")
        (field (name "Manufacturer") "UNI-ROYAL(厚声)")
      )
      (libsource (lib "easyedapro") (part "0402WGF1002TCE"))
    )
    (comp (ref "SW201")
      (value "CPG151101S21")
      (footprint "easyedapro:KEY-TH_CPG1511F01S0X_1")
      (fields (field (name "Manufacturer") "Kailh(凯华)"))
      (libsource (lib "easyedapro") (part "CPG151101S21 RF v1.0"))
    )
    (comp (ref "SW202")
      (value "CPG151101S21")
      (footprint "easyedapro:KEY-TH_CPG1511F01S0X_1")
      (fields (field (name "Manufacturer") "Kailh(凯华)"))
      (libsource (lib "easyedapro") (part "CPG151101S21 RF v1.0"))
    )
    (comp (ref "SW203")
      (value "CPG151101S21")
      (footprint "easyedapro:KEY-TH_CPG1511F01S0X_1")
      (fields (field (name "Manufacturer") "Kailh(凯华)"))
      (libsource (lib "easyedapro") (part "CPG151101S21 RF v1.0"))
    )
    (comp (ref "SW204")
      (value "CPG151101S21")
      (footprint "easyedapro:KEY-TH_CPG1511F01S0X_1")
      (fields (field (name "Manufacturer") "Kailh(凯华)"))
      (libsource (lib "easyedapro") (part "CPG151101S21 RF v1.0"))
    )
    (comp (ref "SW205")
      (value "CPG151101S21")
      (footprint "easyedapro:KEY-TH_CPG1511F01S0X_1")
      (fields (field (name "Manufacturer") "Kailh(凯华)"))
      (libsource (lib "easyedapro") (part "CPG151101S21 RF v1.0"))
    )
    (comp (ref "SW206")
      (value "CPG151101S21")
      (footprint "easyedapro:KEY-TH_CPG1511F01S0X_1")
      (fields (field (name "Manufacturer") "Kailh(凯华)"))
      (libsource (lib "easyedapro") (part "CPG151101S21 RF v1.0"))
    )
    (comp (ref "SW207")
      (value "CPG151101S21")
      (footprint "easyedapro:KEY-TH_CPG1511F01S0X_1")
      (fields (field (name "Manufacturer") "Kailh(凯华)"))
      (libsource (lib "easyedapro") (part "CPG151101S21 RF v1.0"))
    )
    (comp (ref "SW208")
      (value "CPG151101S21")
      (footprint "easyedapro:KEY-TH_CPG1511F01S0X_1")
      (fields (field (name "Manufacturer") "Kailh(凯华)"))
      (libsource (lib "easyedapro") (part "CPG151101S21 RF v1.0"))
    )
    (comp (ref "SW209")
      (value "CPG151101S21")
      (footprint "easyedapro:KEY-TH_CPG1511F01S0X_1")
      (fields (field (name "Manufacturer") "Kailh(凯华)"))
      (libsource (lib "easyedapro") (part "CPG151101S21 RF v1.0"))
    )
    (comp (ref "SW210")
      (value "CPG151101S21")
      (footprint "easyedapro:KEY-TH_CPG1511F01S0X_1")
      (fields (field (name "Manufacturer") "Kailh(凯华)"))
      (libsource (lib "easyedapro") (part "CPG151101S21 RF v1.0"))
    )
    (comp (ref "SW211")
      (value "CPG151101S21")
      (footprint "easyedapro:KEY-TH_CPG1511F01S0X_1")
      (fields (field (name "Manufacturer") "Kailh(凯华)"))
      (libsource (lib "easyedapro") (part "CPG151101S21 RF v1.0"))
    )
    (comp (ref "SW212")
      (value "CPG151101S21")
      (footprint "easyedapro:KEY-TH_CPG1511F01S0X_1")
      (fields (field (name "Manufacturer") "Kailh(凯华)"))
      (libsource (lib "easyedapro") (part "CPG151101S21 RF v1.0"))
    )
    (comp (ref "SW213")
      (value "CPG151101S21")
      (footprint "easyedapro:KEY-TH_CPG1511F01S0X_1")
      (fields (field (name "Manufacturer") "Kailh(凯华)"))
      (libsource (lib "easyedapro") (part "CPG151101S21 RF v1.0"))
    )
    (comp (ref "SW214")
      (value "CPG151101S21")
      (footprint "easyedapro:KEY-TH_CPG1511F01S0X_1")
      (fields (field (name "Manufacturer") "Kailh(凯华)"))
      (libsource (lib "easyedapro") (part "CPG151101S21 RF v1.0"))
    )
    (comp (ref "SW215")
      (value "CPG151101S21")
      (footprint "easyedapro:KEY-TH_CPG1511F01S0X_1")
      (fields (field (name "Manufacturer") "Kailh(凯华)"))
      (libsource (lib "easyedapro") (part "CPG151101S21 RF v1.0"))
    )
    (comp (ref "SW216")
      (value "CPG151101S21")
      (footprint "easyedapro:KEY-TH_CPG1511F01S0X_1")
      (fields (field (name "Manufacturer") "Kailh(凯华)"))
      (libsource (lib "easyedapro") (part "CPG151101S21 RF v1.0"))
    )
    (comp (ref "SW217")
      (value "CPG151101S21")
      (footprint "easyedapro:KEY-TH_CPG1511F01S0X_1")
      (fields (field (name "Manufacturer") "Kailh(凯华)"))
      (libsource (lib "easyedapro") (part "CPG151101S21 RF v1.0"))
    )
    (comp (ref "SW218")
      (value "CPG151101S21")
      (footprint "easyedapro:KEY-TH_CPG1511F01S0X_1")
      (fields (field (name "Manufacturer") "Kailh(凯华)"))
      (libsource (lib "easyedapro") (part "CPG151101S21 RF v1.0"))
    )
    (comp (ref "SW219")
      (value "CPG151101S21")
      (footprint "easyedapro:KEY-TH_CPG1511F01S0X_1")
      (fields (field (name "Manufacturer") "Kailh(凯华)"))
      (libsource (lib "easyedapro") (part "CPG151101S21 RF v1.0"))
    )
    (comp (ref "SW220")
      (value "CPG151101S21")
      (footprint "easyedapro:KEY-TH_CPG1511F01S0X_1")
      (fields (field (name "Manufacturer") "Kailh(凯华)"))
      (libsource (lib "easyedapro") (part "CPG151101S21 RF v1.0"))
    )
    (comp (ref "SW221")
      (value "CPG151101S21")
      (footprint "easyedapro:KEY-TH_CPG1511F01S0X_1")
      (fields (field (name "Manufacturer") "Kailh(凯华)"))
      (libsource (lib "easyedapro") (part "CPG151101S21 RF v1.0"))
    )
    (comp (ref "SW222")
      (value "CPG151101S21")
      (footprint "easyedapro:KEY-TH_CPG1511F01S0X_1")
      (fields (field (name "Manufacturer") "Kailh(凯华)"))
      (libsource (lib "easyedapro") (part "CPG151101S21 RF v1.0"))
    )
    (comp (ref "SW223")
      (value "CPG151101S21")
      (footprint "easyedapro:KEY-TH_CPG1511F01S0X_1")
      (fields (field (name "Manufacturer") "Kailh(凯华)"))
      (libsource (lib "easyedapro") (part "CPG151101S21 RF v1.0"))
    )
    (comp (ref "SW224")
      (value "CPG151101S21")
      (footprint "easyedapro:KEY-TH_CPG1511F01S0X_1")
      (fields (field (name "Manufacturer") "Kailh(凯华)"))
      (libsource (lib "easyedapro") (part "CPG151101S21 RF v1.0"))
    )
    (comp (ref "SW225")
      (value "CPG151101S21")
      (footprint "easyedapro:KEY-TH_CPG1511F01S0X_1")
      (fields (field (name "Manufacturer") "Kailh(凯华)"))
      (libsource (lib "easyedapro") (part "CPG151101S21 RF v1.0"))
    )
    (comp (ref "SW226")
      (value "CPG151101S21")
      (footprint "easyedapro:KEY-TH_CPG1511F01S0X_1")
      (fields (field (name "Manufacturer") "Kailh(凯华)"))
      (libsource (lib "easyedapro") (part "CPG151101S21 RF v1.0"))
    )
    (comp (ref "SW227")
      (value "CPG151101S21")
      (footprint "easyedapro:KEY-TH_CPG1511F01S0X_1")
      (fields (field (name "Manufacturer") "Kailh(凯华)"))
      (libsource (lib "easyedapro") (part "CPG151101S21 RF v1.0"))
    )
    (comp (ref "SW228")
      (value "CPG151101S21")
      (footprint "easyedapro:KEY-TH_CPG1511F01S0X_1")
      (fields (field (name "Manufacturer") "Kailh(凯华)"))
      (libsource (lib "easyedapro") (part "CPG151101S21 RF v1.0"))
    )
    (comp (ref "SW229")
      (value "CPG151101S21")
      (footprint "easyedapro:KEY-TH_CPG1511F01S0X_1")
      (fields (field (name "Manufacturer") "Kailh(凯华)"))
      (libsource (lib "easyedapro") (part "CPG151101S21 RF v1.0"))
    )
    (comp (ref "SW230")
      (value "CPG151101S21")
      (footprint "easyedapro:KEY-TH_CPG1511F01S0X_1")
      (fields (field (name "Manufacturer") "Kailh(凯华)"))
      (libsource (lib "easyedapro") (part "CPG151101S21 RF v1.0"))
    )
    (comp (ref "SW231")
      (value "CPG151101S21")
      (footprint "easyedapro:KEY-TH_CPG1511F01S0X_1")
      (fields (field (name "Manufacturer") "Kailh(凯华)"))
      (libsource (lib "easyedapro") (part "CPG151101S21 RF v1.0"))
    )
    (comp (ref "SW232")
      (value "CPG151101S21")
      (footprint "easyedapro:KEY-TH_CPG1511F01S0X_1")
      (fields (field (name "Manufacturer") "Kailh(凯华)"))
      (libsource (lib "easyedapro") (part "CPG151101S21 RF v1.0"))
    )
    (comp (ref "SW233")
      (value "CPG151101S21")
      (footprint "easyedapro:KEY-TH_CPG1511F01S0X_1")
      (fields (field (name "Manufacturer") "Kailh(凯华)"))
      (libsource (lib "easyedapro") (part "CPG151101S21 RF v1.0"))
    )
    (comp (ref "SW234")
      (value "CPG151101S21")
      (footprint "easyedapro:KEY-TH_CPG1511F01S0X_1")
      (fields (field (name "Manufacturer") "Kailh(凯华)"))
      (libsource (lib "easyedapro") (part "CPG151101S21 RF v1.0"))
    )
    (comp (ref "SW235")
      (value "CPG151101S21")
      (footprint "easyedapro:KEY-TH_CPG1511F01S0X_1")
      (fields (field (name "Manufacturer") "Kailh(凯华)"))
      (libsource (lib "easyedapro") (part "CPG151101S21 RF v1.0"))
    )
    (comp (ref "SW236")
      (value "CPG151101S21")
      (footprint "easyedapro:KEY-TH_CPG1511F01S0X_1")
      (fields (field (name "Manufacturer") "Kailh(凯华)"))
      (libsource (lib "easyedapro") (part "CPG151101S21 RF v1.0"))
    )
    (comp (ref "SW237")
      (value "CPG151101S21")
      (footprint "easyedapro:KEY-TH_CPG1511F01S0X_1")
      (fields (field (name "Manufacturer") "Kailh(凯华)"))
      (libsource (lib "easyedapro") (part "CPG151101S21 RF v1.0"))
    )
    (comp (ref "SW238")
      (value "CPG151101S21")
      (footprint "easyedapro:KEY-TH_CPG1511F01S0X_1")
      (fields (field (name "Manufacturer") "Kailh(凯华)"))
      (libsource (lib "easyedapro") (part "CPG151101S21 RF v1.0"))
    )
    (comp (ref "SW239")
      (value "CPG151101S21")
      (footprint "easyedapro:KEY-TH_CPG1511F01S0X_1")
      (fields (field (name "Manufacturer") "Kailh(凯华)"))
      (libsource (lib "easyedapro") (part "CPG151101S21 RF v1.0"))
    )
    (comp (ref "SW240")
      (value "CPG151101S21")
      (footprint "easyedapro:KEY-TH_CPG1511F01S0X_1")
      (fields (field (name "Manufacturer") "Kailh(凯华)"))
      (libsource (lib "easyedapro") (part "CPG151101S21 RF v1.0"))
    )
    (comp (ref "SW241")
      (value "CPG151101S21")
      (footprint "easyedapro:KEY-TH_CPG1511F01S0X_1")
      (fields (field (name "Manufacturer") "Kailh(凯华)"))
      (libsource (lib "easyedapro") (part "CPG151101S21 RF v1.0"))
    )
    (comp (ref "SW242")
      (value "CPG151101S21")
      (footprint "easyedapro:KEY-TH_CPG1511F01S0X_1")
      (fields (field (name "Manufacturer") "Kailh(凯华)"))
      (libsource (lib "easyedapro") (part "CPG151101S21 RF v1.0"))
    )
    (comp (ref "SW243")
      (value "CPG151101S21")
      (footprint "easyedapro:KEY-TH_CPG1511F01S0X_1")
      (fields (field (name "Manufacturer") "Kailh(凯华)"))
      (libsource (lib "easyedapro") (part "CPG151101S21 RF v1.0"))
    )
    (comp (ref "SW244")
      (value "CPG151101S21")
      (footprint "easyedapro:KEY-TH_CPG1511F01S0X_1")
      (fields (field (name "Manufacturer") "Kailh(凯华)"))
      (libsource (lib "easyedapro") (part "CPG151101S21 RF v1.0"))
    )
    (comp (ref "SW245")
      (value "CPG151101S21")
      (footprint "easyedapro:KEY-TH_CPG1511F01S0X_1")
      (fields (field (name "Manufacturer") "Kailh(凯华)"))
      (libsource (lib "easyedapro") (part "CPG151101S21 RF v1.0"))
    )
    (comp (ref "SW246")
      (value "CPG151101S21")
      (footprint "easyedapro:KEY-TH_CPG1511F01S0X_1")
      (fields (field (name "Manufacturer") "Kailh(凯华)"))
      (libsource (lib "easyedapro") (part "CPG151101S21 RF v1.0"))
    )
    (comp (ref "SW247")
      (value "CPG151101S21")
      (footprint "easyedapro:KEY-TH_CPG1511F01S0X_1")
      (fields (field (name "Manufacturer") "Kailh(凯华)"))
      (libsource (lib "easyedapro") (part "CPG151101S21 RF v1.0"))
    )
    (comp (ref "SW248")
      (value "CPG151101S21")
      (footprint "easyedapro:KEY-TH_CPG1511F01S0X_1")
      (fields (field (name "Manufacturer") "Kailh(凯华)"))
      (libsource (lib "easyedapro") (part "CPG151101S21 RF v1.0"))
    )
    (comp (ref "SW249")
      (value "CPG151101S21")
      (footprint "easyedapro:KEY-TH_CPG1511F01S0X_1")
      (fields (field (name "Manufacturer") "Kailh(凯华)"))
      (libsource (lib "easyedapro") (part "CPG151101S21 RF v1.0"))
    )
    (comp (ref "SW250")
      (value "CPG151101S21")
      (footprint "easyedapro:KEY-TH_CPG1511F01S0X_1")
      (fields (field (name "Manufacturer") "Kailh(凯华)"))
      (libsource (lib "easyedapro") (part "CPG151101S21 RF v1.0"))
    )
    (comp (ref "SW251")
      (value "CPG151101S21")
      (footprint "easyedapro:KEY-TH_CPG1511F01S0X_1")
      (fields (field (name "Manufacturer") "Kailh(凯华)"))
      (libsource (lib "easyedapro") (part "CPG151101S21 RF v1.0"))
    )
    (comp (ref "SW252")
      (value "CPG151101S21")
      (footprint "easyedapro:KEY-TH_CPG1511F01S0X_1")
      (fields (field (name "Manufacturer") "Kailh(凯华)"))
      (libsource (lib "easyedapro") (part "CPG151101S21 RF v1.0"))
    )
    (comp (ref "SW253")
      (value "CPG151101S21")
      (footprint "easyedapro:KEY-TH_CPG1511F01S0X_1")
      (fields (field (name "Manufacturer") "Kailh(凯华)"))
      (libsource (lib "easyedapro") (part "CPG151101S21 RF v1.0"))
    )
    (comp (ref "SW254")
      (value "CPG151101S21")
      (footprint "easyedapro:KEY-TH_CPG1511F01S0X_1")
      (fields (field (name "Manufacturer") "Kailh(凯华)"))
      (libsource (lib "easyedapro") (part "CPG151101S21 RF v1.0"))
    )
    (comp (ref "SW255")
      (value "CPG151101S21")
      (footprint "easyedapro:KEY-TH_CPG1511F01S0X_1")
      (fields (field (name "Manufacturer") "Kailh(凯华)"))
      (libsource (lib "easyedapro") (part "CPG151101S21 RF v1.0"))
    )
    (comp (ref "SW256")
      (value "CPG151101S21")
      (footprint "easyedapro:KEY-TH_CPG1511F01S0X_1")
      (fields (field (name "Manufacturer") "Kailh(凯华)"))
      (libsource (lib "easyedapro") (part "CPG151101S21 RF v1.0"))
    )
    (comp (ref "SW257")
      (value "CPG151101S21")
      (footprint "easyedapro:KEY-TH_CPG1511F01S0X_1")
      (fields (field (name "Manufacturer") "Kailh(凯华)"))
      (libsource (lib "easyedapro") (part "CPG151101S21 RF v1.0"))
    )
    (comp (ref "SW258")
      (value "CPG151101S21")
      (footprint "easyedapro:KEY-TH_CPG1511F01S0X_1")
      (fields (field (name "Manufacturer") "Kailh(凯华)"))
      (libsource (lib "easyedapro") (part "CPG151101S21 RF v1.0"))
    )
    (comp (ref "SW259")
      (value "CPG151101S21")
      (footprint "easyedapro:KEY-TH_CPG1511F01S0X_1")
      (fields (field (name "Manufacturer") "Kailh(凯华)"))
      (libsource (lib "easyedapro") (part "CPG151101S21 RF v1.0"))
    )
    (comp (ref "SW260")
      (value "CPG151101S21")
      (footprint "easyedapro:KEY-TH_CPG1511F01S0X_1")
      (fields (field (name "Manufacturer") "Kailh(凯华)"))
      (libsource (lib "easyedapro") (part "CPG151101S21 RF v1.0"))
    )
    (comp (ref "SW261")
      (value "CPG151101S21")
      (footprint "easyedapro:KEY-TH_CPG1511F01S0X_1")
      (fields (field (name "Manufacturer") "Kailh(凯华)"))
      (libsource (lib "easyedapro") (part "CPG151101S21 RF v1.0"))
    )
    (comp (ref "SW262")
      (value "CPG151101S21")
      (footprint "easyedapro:KEY-TH_CPG1511F01S0X_1")
      (fields (field (name "Manufacturer") "Kailh(凯华)"))
      (libsource (lib "easyedapro") (part "CPG151101S21 RF v1.0"))
    )
    (comp (ref "SW263")
      (value "CPG151101S21")
      (footprint "easyedapro:KEY-TH_CPG1511F01S0X_1")
      (fields (field (name "Manufacturer") "Kailh(凯华)"))
      (libsource (lib "easyedapro") (part "CPG151101S21 RF v1.0"))
    )
    (comp (ref "SW264")
      (value "CPG151101S21")
      (footprint "easyedapro:KEY-TH_CPG1511F01S0X_1")
      (fields (field (name "Manufacturer") "Kailh(凯华)"))
      (libsource (lib "easyedapro") (part "CPG151101S21 RF v1.0"))
    )
    (comp (ref "SW265")
      (value "CPG151101S21")
      (footprint "easyedapro:KEY-TH_CPG1511F01S0X_1")
      (fields (field (name "Manufacturer") "Kailh(凯华)"))
      (libsource (lib "easyedapro") (part "CPG151101S21 RF v1.0"))
    )
    (comp (ref "SW266")
      (value "CPG151101S21")
      (footprint "easyedapro:KEY-TH_CPG1511F01S0X_1")
      (fields (field (name "Manufacturer") "Kailh(凯华)"))
      (libsource (lib "easyedapro") (part "CPG151101S21 RF v1.0"))
    )
    (comp (ref "SW267")
      (value "CPG151101S21")
      (footprint "easyedapro:KEY-TH_CPG1511F01S0X_1")
      (fields (field (name "Manufacturer") "Kailh(凯华)"))
      (libsource (lib "easyedapro") (part "CPG151101S21 RF v1.0"))
    )
    (comp (ref "SW268")
      (value "CPG151101S21")
      (footprint "easyedapro:KEY-TH_CPG1511F01S0X_1")
      (fields (field (name "Manufacturer") "Kailh(凯华)"))
      (libsource (lib "easyedapro") (part "CPG151101S21 RF v1.0"))
    )
    (comp (ref "SW269")
      (value "CPG151101S21")
      (footprint "easyedapro:KEY-TH_CPG1511F01S0X_1")
      (fields (field (name "Manufacturer") "Kailh(凯华)"))
      (libsource (lib "easyedapro") (part "CPG151101S21 RF v1.0"))
    )
    (comp (ref "SW270")
      (value "CPG151101S21")
      (footprint "easyedapro:KEY-TH_CPG1511F01S0X_1")
      (fields (field (name "Manufacturer") "Kailh(凯华)"))
      (libsource (lib "easyedapro") (part "CPG151101S21 RF v1.0"))
    )
    (comp (ref "SW271")
      (value "CPG151101S21")
      (footprint "easyedapro:KEY-TH_CPG1511F01S0X_1")
      (fields (field (name "Manufacturer") "Kailh(凯华)"))
      (libsource (lib "easyedapro") (part "CPG151101S21 RF v1.0"))
    )
    (comp (ref "SW272")
      (value "CPG151101S21")
      (footprint "easyedapro:KEY-TH_CPG1511F01S0X_1")
      (fields (field (name "Manufacturer") "Kailh(凯华)"))
      (libsource (lib "easyedapro") (part "CPG151101S21 RF v1.0"))
    )
    (comp (ref "SW273")
      (value "CPG151101S21")
      (footprint "easyedapro:KEY-TH_CPG1511F01S0X_1")
      (fields (field (name "Manufacturer") "Kailh(凯华)"))
      (libsource (lib "easyedapro") (part "CPG151101S21 RF v1.0"))
    )
    (comp (ref "SW274")
      (value "CPG151101S21")
      (footprint "easyedapro:KEY-TH_CPG1511F01S0X_1")
      (fields (field (name "Manufacturer") "Kailh(凯华)"))
      (libsource (lib "easyedapro") (part "CPG151101S21 RF v1.0"))
    )
    (comp (ref "SW275")
      (value "CPG151101S21")
      (footprint "easyedapro:KEY-TH_CPG1511F01S0X_1")
      (fields (field (name "Manufacturer") "Kailh(凯华)"))
      (libsource (lib "easyedapro") (part "CPG151101S21 RF v1.0"))
    )
    (comp (ref "SW276")
      (value "CPG151101S21")
      (footprint "easyedapro:KEY-TH_CPG1511F01S0X_1")
      (fields (field (name "Manufacturer") "Kailh(凯华)"))
      (libsource (lib "easyedapro") (part "CPG151101S21 RF v1.0"))
    )
    (comp (ref "SW277")
      (value "CPG151101S21")
      (footprint "easyedapro:KEY-TH_CPG1511F01S0X_1")
      (fields (field (name "Manufacturer") "Kailh(凯华)"))
      (libsource (lib "easyedapro") (part "CPG151101S21 RF v1.0"))
    )
    (comp (ref "SW278")
      (value "CPG151101S21")
      (footprint "easyedapro:KEY-TH_CPG1511F01S0X_1")
      (fields (field (name "Manufacturer") "Kailh(凯华)"))
      (libsource (lib "easyedapro") (part "CPG151101S21 RF v1.0"))
    )
  )
  (nets
    (net (code "1") (name "+1V1") (class "Default")
      (node (ref "C107") (pin "2") (pinfunction "2_2") (pintype "unspecified"))
      (node (ref "C108") (pin "2") (pinfunction "2_2") (pintype "unspecified"))
      (node (ref "C109") (pin "2") (pinfunction "2_2") (pintype "unspecified"))
      (node (ref "U101") (pin "23") (pinfunction "DVDD_23") (pintype "bidirectional"))
      (node (ref "U101") (pin "45") (pinfunction "VREG_VOUT_45") (pintype "bidirectional"))
      (node (ref "U101") (pin "50") (pinfunction "DVDD_50") (pintype "bidirectional"))
    )
    (net (code "2") (name "+3V3") (class "Default")
      (node (ref "C101") (pin "2") (pinfunction "2_2") (pintype "unspecified"))
      (node (ref "C102") (pin "2") (pinfunction "2_2") (pintype "unspecified"))
      (node (ref "C103") (pin "2") (pinfunction "2_2") (pintype "unspecified"))
      (node (ref "C104") (pin "2") (pinfunction "2_2") (pintype "unspecified"))
      (node (ref "C106") (pin "2") (pinfunction "2_2") (pintype "unspecified"))
      (node (ref "C112") (pin "2") (pinfunction "2_2") (pintype "unspecified"))
      (node (ref "C113") (pin "2") (pinfunction "2_2") (pintype "unspecified"))
      (node (ref "C114") (pin "2") (pinfunction "2_2") (pintype "unspecified"))
      (node (ref "C115") (pin "2") (pinfunction "2_2") (pintype "unspecified"))
      (node (ref "C116") (pin "2") (pinfunction "2_2") (pintype "unspecified"))
      (node (ref "C126") (pin "2") (pinfunction "2_2") (pintype "unspecified"))
      (node (ref "C201") (pin "2") (pinfunction "2_2") (pintype "unspecified"))
      (node (ref "R101") (pin "1") (pinfunction "1_1") (pintype "input"))
      (node (ref "R104") (pin "2") (pinfunction "2_2") (pintype "input"))
      (node (ref "R122") (pin "2") (pinfunction "2_2") (pintype "input"))
      (node (ref "R123") (pin "2") (pinfunction "2_2") (pintype "input"))
      (node (ref "R201") (pin "2") (pinfunction "2_2") (pintype "input"))
      (node (ref "R202") (pin "2") (pinfunction "2_2") (pintype "input"))
      (node (ref "R223") (pin "2") (pinfunction "2_2") (pintype "input"))
      (node (ref "R224") (pin "2") (pinfunction "2_2") (pintype "input"))
      (node (ref "U101") (pin "1") (pinfunction "IOVDD_1") (pintype "bidirectional"))
      (node (ref "U101") (pin "10") (pinfunction "IOVDD_10") (pintype "bidirectional"))
      (node (ref "U101") (pin "22") (pinfunction "IOVDD_22") (pintype "bidirectional"))
      (node (ref "U101") (pin "33") (pinfunction "IOVDD_33") (pintype "bidirectional"))
      (node (ref "U101") (pin "42") (pinfunction "IOVDD_42") (pintype "bidirectional"))
      (node (ref "U101") (pin "44") (pinfunction "VREG_IN_44") (pintype "bidirectional"))
      (node (ref "U101") (pin "48") (pinfunction "USB_VDD_48") (pintype "bidirectional"))
      (node (ref "U101") (pin "49") (pinfunction "IOVDD_49") (pintype "bidirectional"))
      (node (ref "U102") (pin "3") (pinfunction "OUT_3") (pintype "unspecified"))
      (node (ref "U104") (pin "8") (pinfunction "VCC_8") (pintype "unspecified"))
    )
    (net (code "3") (name "+3V3_A") (class "Default")
      (node (ref "C105") (pin "2") (pinfunction "2_2") (pintype "unspecified"))
      (node (ref "R101") (pin "2") (pinfunction "2_2") (pintype "input"))
      (node (ref "U101") (pin "43") (pinfunction "ADC_AVDD_43") (pintype "bidirectional"))
    )
    (net (code "4") (name "+5V_USB") (class "Default")
      (node (ref "C111") (pin "2") (pinfunction "2_2") (pintype "unspecified"))
      (node (ref "C118") (pin "2") (pinfunction "2_2") (pintype "unspecified"))
      (node (ref "C119") (pin "2") (pinfunction "2_2") (pintype "unspecified"))
      (node (ref "D101") (pin "2") (pinfunction "2_2") (pintype "input"))
      (node (ref "D102") (pin "2") (pinfunction "2_2") (pintype "input"))
      (node (ref "J101") (pin "11") (pinfunction "VBUS_11") (pintype "unspecified"))
      (node (ref "J101") (pin "2") (pinfunction "VBUS_2") (pintype "unspecified"))
      (node (ref "U102") (pin "1") (pinfunction "IN_1") (pintype "unspecified"))
    )
    (net (code "5") (name "COL0") (class "Default")
      (node (ref "J201") (pin "1") (pinfunction "1_1") (pintype "input"))
      (node (ref "J204") (pin "1") (pinfunction "1_1") (pintype "input"))
      (node (ref "J207") (pin "1") (pinfunction "1_1") (pintype "input"))
      (node (ref "J240") (pin "1") (pinfunction "1_1") (pintype "input"))
      (node (ref "J243") (pin "1") (pinfunction "1_1") (pintype "input"))
      (node (ref "J246") (pin "1") (pinfunction "1_1") (pintype "input"))
      (node (ref "R108") (pin "2") (pinfunction "2_2") (pintype "input"))
    )
    (net (code "6") (name "COL0_R") (class "Default")
      (node (ref "R108") (pin "1") (pinfunction "1_1") (pintype "input"))
      (node (ref "U101") (pin "2") (pinfunction "GPIO0_2") (pintype "bidirectional"))
    )
    (net (code "7") (name "COL1") (class "Default")
      (node (ref "J202") (pin "1") (pinfunction "1_1") (pintype "input"))
      (node (ref "J205") (pin "1") (pinfunction "1_1") (pintype "input"))
      (node (ref "J208") (pin "1") (pinfunction "1_1") (pintype "input"))
      (node (ref "J241") (pin "1") (pinfunction "1_1") (pintype "input"))
      (node (ref "J244") (pin "1") (pinfunction "1_1") (pintype "input"))
      (node (ref "J247") (pin "1") (pinfunction "1_1") (pintype "input"))
      (node (ref "R110") (pin "2") (pinfunction "2_2") (pintype "input"))
    )
    (net (code "8") (name "COL1_R") (class "Default")
      (node (ref "R110") (pin "1") (pinfunction "1_1") (pintype "input"))
      (node (ref "U101") (pin "3") (pinfunction "GPIO1_3") (pintype "bidirectional"))
    )
    (net (code "9") (name "COL2") (class "Default")
      (node (ref "J203") (pin "1") (pinfunction "1_1") (pintype "input"))
      (node (ref "J206") (pin "1") (pinfunction "1_1") (pintype "input"))
      (node (ref "J209") (pin "1") (pinfunction "1_1") (pintype "input"))
      (node (ref "J242") (pin "1") (pinfunction "1_1") (pintype "input"))
      (node (ref "J245") (pin "1") (pinfunction "1_1") (pintype "input"))
      (node (ref "J248") (pin "1") (pinfunction "1_1") (pintype "input"))
      (node (ref "R112") (pin "2") (pinfunction "2_2") (pintype "input"))
    )
    (net (code "10") (name "COL2_R") (class "Default")
      (node (ref "R112") (pin "1") (pinfunction "1_1") (pintype "input"))
      (node (ref "U101") (pin "4") (pinfunction "GPIO2_4") (pintype "bidirectional"))
    )
    (net (code "11") (name "COL3") (class "Default")
      (node (ref "J210") (pin "1") (pinfunction "1_1") (pintype "input"))
      (node (ref "J213") (pin "1") (pinfunction "1_1") (pintype "input"))
      (node (ref "J216") (pin "1") (pinfunction "1_1") (pintype "input"))
      (node (ref "J249") (pin "1") (pinfunction "1_1") (pintype "input"))
      (node (ref "J252") (pin "1") (pinfunction "1_1") (pintype "input"))
      (node (ref "J255") (pin "1") (pinfunction "1_1") (pintype "input"))
      (node (ref "R113") (pin "2") (pinfunction "2_2") (pintype "input"))
    )
    (net (code "12") (name "COL3_R") (class "Default")
      (node (ref "R113") (pin "1") (pinfunction "1_1") (pintype "input"))
      (node (ref "U101") (pin "5") (pinfunction "GPIO3_5") (pintype "bidirectional"))
    )
    (net (code "13") (name "COL4") (class "Default")
      (node (ref "J211") (pin "1") (pinfunction "1_1") (pintype "input"))
      (node (ref "J214") (pin "1") (pinfunction "1_1") (pintype "input"))
      (node (ref "J217") (pin "1") (pinfunction "1_1") (pintype "input"))
      (node (ref "J250") (pin "1") (pinfunction "1_1") (pintype "input"))
      (node (ref "J253") (pin "1") (pinfunction "1_1") (pintype "input"))
      (node (ref "J256") (pin "1") (pinfunction "1_1") (pintype "input"))
      (node (ref "R208") (pin "2") (pinfunction "2_2") (pintype "input"))
    )
    (net (code "14") (name "COL4_R") (class "Default")
      (node (ref "R208") (pin "1") (pinfunction "1_1") (pintype "input"))
      (node (ref "U101") (pin "6") (pinfunction "GPIO4_6") (pintype "bidirectional"))
    )
    (net (code "15") (name "COL5") (class "Default")
      (node (ref "J212") (pin "1") (pinfunction "1_1") (pintype "input"))
      (node (ref "J215") (pin "1") (pinfunction "1_1") (pintype "input"))
      (node (ref "J218") (pin "1") (pinfunction "1_1") (pintype "input"))
      (node (ref "J251") (pin "1") (pinfunction "1_1") (pintype "input"))
      (node (ref "J254") (pin "1") (pinfunction "1_1") (pintype "input"))
      (node (ref "J257") (pin "1") (pinfunction "1_1") (pintype "input"))
      (node (ref "R209") (pin "2") (pinfunction "2_2") (pintype "input"))
    )
    (net (code "16") (name "COL5_R") (class "Default")
      (node (ref "R209") (pin "1") (pinfunction "1_1") (pintype "input"))
      (node (ref "U101") (pin "7") (pinfunction "GPIO5_7") (pintype "bidirectional"))
    )
    (net (code "17") (name "COL6") (class "Default")
      (node (ref "J219") (pin "1") (pinfunction "1_1") (pintype "input"))
      (node (ref "J222") (pin "1") (pinfunction "1_1") (pintype "input"))
      (node (ref "J225") (pin "1") (pinfunction "1_1") (pintype "input"))
      (node (ref "J258") (pin "1") (pinfunction "1_1") (pintype "input"))
      (node (ref "J261") (pin "1") (pinfunction "1_1") (pintype "input"))
      (node (ref "J264") (pin "1") (pinfunction "1_1") (pintype "input"))
      (node (ref "R210") (pin "2") (pinfunction "2_2") (pintype "input"))
    )
    (net (code "18") (name "COL6_R") (class "Default")
      (node (ref "R210") (pin "1") (pinfunction "1_1") (pintype "input"))
      (node (ref "U101") (pin "8") (pinfunction "GPIO6_8") (pintype "bidirectional"))
    )
    (net (code "19") (name "COL7") (class "Default")
      (node (ref "J220") (pin "1") (pinfunction "1_1") (pintype "input"))
      (node (ref "J223") (pin "1") (pinfunction "1_1") (pintype "input"))
      (node (ref "J226") (pin "1") (pinfunction "1_1") (pintype "input"))
      (node (ref "J259") (pin "1") (pinfunction "1_1") (pintype "input"))
      (node (ref "J262") (pin "1") (pinfunction "1_1") (pintype "input"))
      (node (ref "J265") (pin "1") (pinfunction "1_1") (pintype "input"))
      (node (ref "R211") (pin "2") (pinfunction "2_2") (pintype "input"))
    )
    (net (code "20") (name "COL7_R") (class "Default")
      (node (ref "R211") (pin "1") (pinfunction "1_1") (pintype "input"))
      (node (ref "U101") (pin "9") (pinfunction "GPIO7_9") (pintype "bidirectional"))
    )
    (net (code "21") (name "COL8") (class "Default")
      (node (ref "J221") (pin "1") (pinfunction "1_1") (pintype "input"))
      (node (ref "J224") (pin "1") (pinfunction "1_1") (pintype "input"))
      (node (ref "J227") (pin "1") (pinfunction "1_1") (pintype "input"))
      (node (ref "J260") (pin "1") (pinfunction "1_1") (pintype "input"))
      (node (ref "J263") (pin "1") (pinfunction "1_1") (pintype "input"))
      (node (ref "J266") (pin "1") (pinfunction "1_1") (pintype "input"))
      (node (ref "R212") (pin "2") (pinfunction "2_2") (pintype "input"))
    )
    (net (code "22") (name "COL8_R") (class "Default")
      (node (ref "R212") (pin "1") (pinfunction "1_1") (pintype "input"))
      (node (ref "U101") (pin "11") (pinfunction "GPIO8_11") (pintype "bidirectional"))
    )
    (net (code "23") (name "COL9") (class "Default")
      (node (ref "J228") (pin "1") (pinfunction "1_1") (pintype "input"))
      (node (ref "J231") (pin "1") (pinfunction "1_1") (pintype "input"))
      (node (ref "J234") (pin "1") (pinfunction "1_1") (pintype "input"))
      (node (ref "J267") (pin "1") (pinfunction "1_1") (pintype "input"))
      (node (ref "J270") (pin "1") (pinfunction "1_1") (pintype "input"))
      (node (ref "J273") (pin "1") (pinfunction "1_1") (pintype "input"))
      (node (ref "R213") (pin "2") (pinfunction "2_2") (pintype "input"))
    )
    (net (code "24") (name "COL9_R") (class "Default")
      (node (ref "R213") (pin "1") (pinfunction "1_1") (pintype "input"))
      (node (ref "U101") (pin "12") (pinfunction "GPIO9_12") (pintype "bidirectional"))
    )
    (net (code "25") (name "COL10") (class "Default")
      (node (ref "J229") (pin "1") (pinfunction "1_1") (pintype "input"))
      (node (ref "J232") (pin "1") (pinfunction "1_1") (pintype "input"))
      (node (ref "J235") (pin "1") (pinfunction "1_1") (pintype "input"))
      (node (ref "J268") (pin "1") (pinfunction "1_1") (pintype "input"))
      (node (ref "J271") (pin "1") (pinfunction "1_1") (pintype "input"))
      (node (ref "J274") (pin "1") (pinfunction "1_1") (pintype "input"))
      (node (ref "R214") (pin "2") (pinfunction "2_2") (pintype "input"))
    )
    (net (code "26") (name "COL10_R") (class "Default")
      (node (ref "R214") (pin "1") (pinfunction "1_1") (pintype "input"))
      (node (ref "U101") (pin "13") (pinfunction "GPIO10_13") (pintype "bidirectional"))
    )
    (net (code "27") (name "COL11") (class "Default")
      (node (ref "J230") (pin "1") (pinfunction "1_1") (pintype "input"))
      (node (ref "J233") (pin "1") (pinfunction "1_1") (pintype "input"))
      (node (ref "J236") (pin "1") (pinfunction "1_1") (pintype "input"))
      (node (ref "J269") (pin "1") (pinfunction "1_1") (pintype "input"))
      (node (ref "J272") (pin "1") (pinfunction "1_1") (pintype "input"))
      (node (ref "J275") (pin "1") (pinfunction "1_1") (pintype "input"))
      (node (ref "R215") (pin "2") (pinfunction "2_2") (pintype "input"))
    )
    (net (code "28") (name "COL11_R") (class "Default")
      (node (ref "R215") (pin "1") (pinfunction "1_1") (pintype "input"))
      (node (ref "U101") (pin "14") (pinfunction "GPIO11_14") (pintype "bidirectional"))
    )
    (net (code "29") (name "COL12") (class "Default")
      (node (ref "J237") (pin "1") (pinfunction "1_1") (pintype "input"))
      (node (ref "J238") (pin "1") (pinfunction "1_1") (pintype "input"))
      (node (ref "J239") (pin "1") (pinfunction "1_1") (pintype "input"))
      (node (ref "J276") (pin "1") (pinfunction "1_1") (pintype "input"))
      (node (ref "J277") (pin "1") (pinfunction "1_1") (pintype "input"))
      (node (ref "J278") (pin "1") (pinfunction "1_1") (pintype "input"))
      (node (ref "R216") (pin "2") (pinfunction "2_2") (pintype "input"))
    )
    (net (code "30") (name "COL12_R") (class "Default")
      (node (ref "R216") (pin "1") (pinfunction "1_1") (pintype "input"))
      (node (ref "U101") (pin "15") (pinfunction "GPIO12_15") (pintype "bidirectional"))
    )
    (net (code "31") (name "CON_USB_N") (class "Default")
      (node (ref "D103") (pin "2") (pinfunction "2_2") (pintype "input"))
      (node (ref "J101") (pin "5") (pinfunction "DN2_5") (pintype "unspecified"))
      (node (ref "J101") (pin "7") (pinfunction "DN1_7") (pintype "unspecified"))
      (node (ref "R109") (pin "1") (pinfunction "1_1") (pintype "input"))
    )
    (net (code "32") (name "CON_USB_P") (class "Default")
      (node (ref "D104") (pin "2") (pinfunction "2_2") (pintype "input"))
      (node (ref "J101") (pin "6") (pinfunction "DP1_6") (pintype "unspecified"))
      (node (ref "J101") (pin "8") (pinfunction "DP2_8") (pintype "unspecified"))
      (node (ref "R111") (pin "1") (pinfunction "1_1") (pintype "input"))
    )
    (net (code "33") (name "CS") (class "Default")
      (node (ref "FPC1") (pin "5") (pinfunction "5_5") (pintype "unspecified"))
      (node (ref "U101") (pin "32") (pinfunction "GPIO21_32") (pintype "bidirectional"))
    )
    (net (code "34") (name "ENC1_A") (class "Default")
      (node (ref "C203") (pin "2") (pinfunction "2_2") (pintype "input"))
      (node (ref "R205") (pin "1") (pinfunction "1_1") (pintype "input"))
      (node (ref "U101") (pin "30") (pinfunction "GPIO19_30") (pintype "bidirectional"))
    )
    (net (code "35") (name "ENC1_B") (class "Default")
      (node (ref "C204") (pin "2") (pinfunction "2_2") (pintype "input"))
      (node (ref "R207") (pin "1") (pinfunction "1_1") (pintype "input"))
      (node (ref "U101") (pin "31") (pinfunction "GPIO20_31") (pintype "bidirectional"))
    )
    (net (code "36") (name "GND") (class "Default")
      (node (ref "C101") (pin "1") (pinfunction "1_1") (pintype "unspecified"))
      (node (ref "C102") (pin "1") (pinfunction "1_1") (pintype "unspecified"))
      (node (ref "C103") (pin "1") (pinfunction "1_1") (pintype "unspecified"))
      (node (ref "C104") (pin "1") (pinfunction "1_1") (pintype "unspecified"))
      (node (ref "C105") (pin "1") (pinfunction "1_1") (pintype "unspecified"))
      (node (ref "C106") (pin "1") (pinfunction "1_1") (pintype "unspecified"))
      (node (ref "C107") (pin "1") (pinfunction "1_1") (pintype "unspecified"))
      (node (ref "C108") (pin "1") (pinfunction "1_1") (pintype "unspecified"))
      (node (ref "C109") (pin "1") (pinfunction "1_1") (pintype "unspecified"))
      (node (ref "C111") (pin "1") (pinfunction "1_1") (pintype "unspecified"))
      (node (ref "C112") (pin "1") (pinfunction "1_1") (pintype "unspecified"))
      (node (ref "C113") (pin "1") (pinfunction "1_1") (pintype "unspecified"))
      (node (ref "C114") (pin "1") (pinfunction "1_1") (pintype "unspecified"))
      (node (ref "C115") (pin "1") (pinfunction "1_1") (pintype "unspecified"))
      (node (ref "C116") (pin "1") (pinfunction "1_1") (pintype "unspecified"))
      (node (ref "C118") (pin "1") (pinfunction "1_1") (pintype "unspecified"))
      (node (ref "C119") (pin "1") (pinfunction "1_1") (pintype "unspecified"))
      (node (ref "C123") (pin "2") (pinfunction "2_2") (pintype "unspecified"))
      (node (ref "C124") (pin "2") (pinfunction "2_2") (pintype "unspecified"))
      (node (ref "C126") (pin "1") (pinfunction "1_1") (pintype "unspecified"))
      (node (ref "C127") (pin "1") (pinfunction "1_1") (pintype "unspecified"))
      (node (ref "C201") (pin "1") (pinfunction "1_1") (pintype "unspecified"))
      (node (ref "C203") (pin "1") (pinfunction "1_1") (pintype "input"))
      (node (ref "C204") (pin "1") (pinfunction "1_1") (pintype "input"))
      (node (ref "D101") (pin "1") (pinfunction "1_1") (pintype "input"))
      (node (ref "D102") (pin "1") (pinfunction "1_1") (pintype "input"))
      (node (ref "D103") (pin "1") (pinfunction "1_1") (pintype "input"))
      (node (ref "D104") (pin "1") (pinfunction "1_1") (pintype "input"))
      (node (ref "ENC201") (pin "3") (pinfunction "3_3") (pintype "input"))
      (node (ref "ENC201") (pin "4") (pinfunction "4_4") (pintype "input"))
      (node (ref "ENC201") (pin "C") (pinfunction "C_C") (pintype "input"))
      (node (ref "FPC1") (pin "10") (pinfunction "10_10") (pintype "unspecified"))
      (node (ref "FPC1") (pin "8") (pinfunction "8_8") (pintype "unspecified"))
      (node (ref "J101") (pin "1") (pinfunction "GND_1") (pintype "unspecified"))
      (node (ref "J101") (pin "12") (pinfunction "GND_12") (pintype "unspecified"))
      (node (ref "J101") (pin "13") (pinfunction "SHELL_13") (pintype "unspecified"))
      (node (ref "J101") (pin "14") (pinfunction "SHELL_14") (pintype "unspecified"))
      (node (ref "J102") (pin "2") (pinfunction "2_2") (pintype "input"))
      (node (ref "LED102") (pin "2") (pinfunction "K_2") (pintype "unspecified"))
      (node (ref "MH201") (pin "1") (pinfunction "1_1") (pintype "input"))
      (node (ref "MH202") (pin "1") (pinfunction "1_1") (pintype "input"))
      (node (ref "MH203") (pin "1") (pinfunction "1_1") (pintype "input"))
      (node (ref "MH204") (pin "1") (pinfunction "1_1") (pintype "input"))
      (node (ref "MH205") (pin "1") (pinfunction "1_1") (pintype "input"))
      (node (ref "MH206") (pin "1") (pinfunction "1_1") (pintype "input"))
      (node (ref "MH207") (pin "1") (pinfunction "1_1") (pintype "input"))
      (node (ref "MH208") (pin "1") (pinfunction "1_1") (pintype "input"))
      (node (ref "R118") (pin "1") (pinfunction "1_1") (pintype "input"))
      (node (ref "R119") (pin "1") (pinfunction "1_1") (pintype "input"))
      (node (ref "SW101") (pin "1") (pinfunction "A_1") (pintype "input"))
      (node (ref "SW101") (pin "2") (pinfunction "B_2") (pintype "input"))
      (node (ref "SW102") (pin "1") (pinfunction "A_1") (pintype "input"))
      (node (ref "SW102") (pin "2") (pinfunction "B_2") (pintype "input"))
      (node (ref "U101") (pin "19") (pinfunction "TESTEN_19") (pintype "unspecified"))
      (node (ref "U101") (pin "57") (pinfunction "GND_57") (pintype "bidirectional"))
      (node (ref "U102") (pin "2") (pinfunction "GND_2") (pintype "unspecified"))
      (node (ref "U102") (pin "4") (pinfunction "GND_4") (pintype "unspecified"))
      (node (ref "U104") (pin "4") (pinfunction "GND_4") (pintype "unspecified"))
      (node (ref "Y101") (pin "2") (pinfunction "GND_2") (pintype "input"))
      (node (ref "Y101") (pin "4") (pinfunction "GND_4") (pintype "input"))
    )
    (net (code "37") (name "Net-(D201-A)") (class "Default")
      (node (ref "D201") (pin "2") (pinfunction "A_2") (pintype "input"))
      (node (ref "J201") (pin "2") (pinfunction "2_2") (pintype "input"))
    )
    (net (code "38") (name "Net-(D202-A)") (class "Default")
      (node (ref "D202") (pin "2") (pinfunction "A_2") (pintype "input"))
      (node (ref "J202") (pin "2") (pinfunction "2_2") (pintype "input"))
    )
    (net (code "39") (name "Net-(D203-A)") (class "Default")
      (node (ref "D203") (pin "2") (pinfunction "A_2") (pintype "input"))
      (node (ref "J203") (pin "2") (pinfunction "2_2") (pintype "input"))
    )
    (net (code "40") (name "Net-(D204-A)") (class "Default")
      (node (ref "D204") (pin "2") (pinfunction "A_2") (pintype "input"))
      (node (ref "J204") (pin "2") (pinfunction "2_2") (pintype "input"))
    )
    (net (code "41") (name "Net-(D205-A)") (class "Default")
      (node (ref "D205") (pin "2") (pinfunction "A_2") (pintype "input"))
      (node (ref "J205") (pin "2") (pinfunction "2_2") (pintype "input"))
    )
    (net (code "42") (name "Net-(D206-A)") (class "Default")
      (node (ref "D206") (pin "2") (pinfunction "A_2") (pintype "input"))
      (node (ref "J206") (pin "2") (pinfunction "2_2") (pintype "input"))
    )
    (net (code "43") (name "Net-(D207-A)") (class "Default")
      (node (ref "D207") (pin "2") (pinfunction "A_2") (pintype "input"))
      (node (ref "J207") (pin "2") (pinfunction "2_2") (pintype "input"))
    )
    (net (code "44") (name "Net-(D208-A)") (class "Default")
      (node (ref "D208") (pin "2") (pinfunction "A_2") (pintype "input"))
      (node (ref "J208") (pin "2") (pinfunction "2_2") (pintype "input"))
    )
    (net (code "45") (name "Net-(D209-A)") (class "Default")
      (node (ref "D209") (pin "2") (pinfunction "A_2") (pintype "input"))
      (node (ref "J209") (pin "2") (pinfunction "2_2") (pintype "input"))
    )
    (net (code "46") (name "Net-(D213-A)") (class "Default")
      (node (ref "D213") (pin "2") (pinfunction "A_2") (pintype "input"))
      (node (ref "J210") (pin "2") (pinfunction "2_2") (pintype "input"))
    )
    (net (code "47") (name "Net-(D214-A)") (class "Default")
      (node (ref "D214") (pin "2") (pinfunction "A_2") (pintype "input"))
      (node (ref "J211") (pin "2") (pinfunction "2_2") (pintype "input"))
    )
    (net (code "48") (name "Net-(D215-A)") (class "Default")
      (node (ref "D215") (pin "2") (pinfunction "A_2") (pintype "input"))
      (node (ref "J212") (pin "2") (pinfunction "2_2") (pintype "input"))
    )
    (net (code "49") (name "Net-(D216-A)") (class "Default")
      (node (ref "D216") (pin "2") (pinfunction "A_2") (pintype "input"))
      (node (ref "J213") (pin "2") (pinfunction "2_2") (pintype "input"))
    )
    (net (code "50") (name "Net-(D217-A)") (class "Default")
      (node (ref "D217") (pin "2") (pinfunction "A_2") (pintype "input"))
      (node (ref "J214") (pin "2") (pinfunction "2_2") (pintype "input"))
    )
    (net (code "51") (name "Net-(D218-A)") (class "Default")
      (node (ref "D218") (pin "2") (pinfunction "A_2") (pintype "input"))
      (node (ref "J215") (pin "2") (pinfunction "2_2") (pintype "input"))
    )
    (net (code "52") (name "Net-(D219-A)") (class "Default")
      (node (ref "D219") (pin "2") (pinfunction "A_2") (pintype "input"))
      (node (ref "J216") (pin "2") (pinfunction "2_2") (pintype "input"))
    )
    (net (code "53") (name "Net-(D220-A)") (class "Default")
      (node (ref "D220") (pin "2") (pinfunction "A_2") (pintype "input"))
      (node (ref "J217") (pin "2") (pinfunction "2_2") (pintype "input"))
    )
    (net (code "54") (name "Net-(D221-A)") (class "Default")
      (node (ref "D221") (pin "2") (pinfunction "A_2") (pintype "input"))
      (node (ref "J218") (pin "2") (pinfunction "2_2") (pintype "input"))
    )
    (net (code "55") (name "Net-(D225-A)") (class "Default")
      (node (ref "D225") (pin "2") (pinfunction "A_2") (pintype "input"))
      (node (ref "J219") (pin "2") (pinfunction "2_2") (pintype "input"))
    )
    (net (code "56") (name "Net-(D226-A)") (class "Default")
      (node (ref "D226") (pin "2") (pinfunction "A_2") (pintype "input"))
      (node (ref "J220") (pin "2") (pinfunction "2_2") (pintype "input"))
    )
    (net (code "57") (name "Net-(D227-A)") (class "Default")
      (node (ref "D227") (pin "2") (pinfunction "A_2") (pintype "input"))
      (node (ref "J221") (pin "2") (pinfunction "2_2") (pintype "input"))
    )
    (net (code "58") (name "Net-(D228-A)") (class "Default")
      (node (ref "D228") (pin "2") (pinfunction "A_2") (pintype "input"))
      (node (ref "J222") (pin "2") (pinfunction "2_2") (pintype "input"))
    )
    (net (code "59") (name "Net-(D229-A)") (class "Default")
      (node (ref "D229") (pin "2") (pinfunction "A_2") (pintype "input"))
      (node (ref "J223") (pin "2") (pinfunction "2_2") (pintype "input"))
    )
    (net (code "60") (name "Net-(D230-A)") (class "Default")
      (node (ref "D230") (pin "2") (pinfunction "A_2") (pintype "input"))
      (node (ref "J224") (pin "2") (pinfunction "2_2") (pintype "input"))
    )
    (net (code "61") (name "Net-(D231-A)") (class "Default")
      (node (ref "D231") (pin "2") (pinfunction "A_2") (pintype "input"))
      (node (ref "J225") (pin "2") (pinfunction "2_2") (pintype "input"))
    )
    (net (code "62") (name "Net-(D232-A)") (class "Default")
      (node (ref "D232") (pin "2") (pinfunction "A_2") (pintype "input"))
      (node (ref "J226") (pin "2") (pinfunction "2_2") (pintype "input"))
    )
    (net (code "63") (name "Net-(D233-A)") (class "Default")
      (node (ref "D233") (pin "2") (pinfunction "A_2") (pintype "input"))
      (node (ref "J227") (pin "2") (pinfunction "2_2") (pintype "input"))
    )
    (net (code "64") (name "Net-(D237-A)") (class "Default")
      (node (ref "D237") (pin "2") (pinfunction "A_2") (pintype "input"))
      (node (ref "J228") (pin "2") (pinfunction "2_2") (pintype "input"))
    )
    (net (code "65") (name "Net-(D238-A)") (class "Default")
      (node (ref "D238") (pin "2") (pinfunction "A_2") (pintype "input"))
      (node (ref "J229") (pin "2") (pinfunction "2_2") (pintype "input"))
    )
    (net (code "66") (name "Net-(D239-A)") (class "Default")
      (node (ref "D239") (pin "2") (pinfunction "A_2") (pintype "input"))
      (node (ref "J230") (pin "2") (pinfunction "2_2") (pintype "input"))
    )
    (net (code "67") (name "Net-(D240-A)") (class "Default")
      (node (ref "D240") (pin "2") (pinfunction "A_2") (pintype "input"))
      (node (ref "J231") (pin "2") (pinfunction "2_2") (pintype "input"))
    )
    (net (code "68") (name "Net-(D241-A)") (class "Default")
      (node (ref "D241") (pin "2") (pinfunction "A_2") (pintype "input"))
      (node (ref "J232") (pin "2") (pinfunction "2_2") (pintype "input"))
    )
    (net (code "69") (name "Net-(D242-A)") (class "Default")
      (node (ref "D242") (pin "2") (pinfunction "A_2") (pintype "input"))
      (node (ref "J233") (pin "2") (pinfunction "2_2") (pintype "input"))
    )
    (net (code "70") (name "Net-(D243-A)") (class "Default")
      (node (ref "D243") (pin "2") (pinfunction "A_2") (pintype "input"))
      (node (ref "J234") (pin "2") (pinfunction "2_2") (pintype "input"))
    )
    (net (code "71") (name "Net-(D244-A)") (class "Default")
      (node (ref "D244") (pin "2") (pinfunction "A_2") (pintype "input"))
      (node (ref "J235") (pin "2") (pinfunction "2_2") (pintype "input"))
    )
    (net (code "72") (name "Net-(D245-A)") (class "Default")
      (node (ref "D245") (pin "2") (pinfunction "A_2") (pintype "input"))
      (node (ref "J236") (pin "2") (pinfunction "2_2") (pintype "input"))
    )
    (net (code "73") (name "Net-(D249-A)") (class "Default")
      (node (ref "D249") (pin "2") (pinfunction "A_2") (pintype "input"))
      (node (ref "J237") (pin "2") (pinfunction "2_2") (pintype "input"))
    )
    (net (code "74") (name "Net-(D250-A)") (class "Default")
      (node (ref "D250") (pin "2") (pinfunction "A_2") (pintype "input"))
      (node (ref "J238") (pin "2") (pinfunction "2_2") (pintype "input"))
    )
    (net (code "75") (name "Net-(D251-A)") (class "Default")
      (node (ref "D251") (pin "2") (pinfunction "A_2") (pintype "input"))
      (node (ref "J239") (pin "2") (pinfunction "2_2") (pintype "input"))
    )
    (net (code "76") (name "Net-(D252-A)") (class "Default")
      (node (ref "D252") (pin "2") (pinfunction "A_2") (pintype "input"))
      (node (ref "J240") (pin "2") (pinfunction "2_2") (pintype "input"))
    )
    (net (code "77") (name "Net-(D253-A)") (class "Default")
      (node (ref "D253") (pin "2") (pinfunction "A_2") (pintype "input"))
      (node (ref "J241") (pin "2") (pinfunction "2_2") (pintype "input"))
    )
    (net (code "78") (name "Net-(D254-A)") (class "Default")
      (node (ref "D254") (pin "2") (pinfunction "A_2") (pintype "input"))
      (node (ref "J242") (pin "2") (pinfunction "2_2") (pintype "input"))
    )
    (net (code "79") (name "Net-(D255-A)") (class "Default")
      (node (ref "D255") (pin "2") (pinfunction "A_2") (pintype "input"))
      (node (ref "J243") (pin "2") (pinfunction "2_2") (pintype "input"))
    )
    (net (code "80") (name "Net-(D256-A)") (class "Default")
      (node (ref "D256") (pin "2") (pinfunction "A_2") (pintype "input"))
      (node (ref "J244") (pin "2") (pinfunction "2_2") (pintype "input"))
    )
    (net (code "81") (name "Net-(D257-A)") (class "Default")
      (node (ref "D257") (pin "2") (pinfunction "A_2") (pintype "input"))
      (node (ref "J245") (pin "2") (pinfunction "2_2") (pintype "input"))
    )
    (net (code "82") (name "Net-(D258-A)") (class "Default")
      (node (ref "D258") (pin "2") (pinfunction "A_2") (pintype "input"))
      (node (ref "J246") (pin "2") (pinfunction "2_2") (pintype "input"))
    )
    (net (code "83") (name "Net-(D259-A)") (class "Default")
      (node (ref "D259") (pin "2") (pinfunction "A_2") (pintype "input"))
      (node (ref "J247") (pin "2") (pinfunction "2_2") (pintype "input"))
    )
    (net (code "84") (name "Net-(D260-A)") (class "Default")
      (node (ref "D260") (pin "2") (pinfunction "A_2") (pintype "input"))
      (node (ref "J248") (pin "2") (pinfunction "2_2") (pintype "input"))
    )
    (net (code "85") (name "Net-(D261-A)") (class "Default")
      (node (ref "D261") (pin "2") (pinfunction "A_2") (pintype "input"))
      (node (ref "J249") (pin "2") (pinfunction "2_2") (pintype "input"))
    )
    (net (code "86") (name "Net-(D262-A)") (class "Default")
      (node (ref "D262") (pin "2") (pinfunction "A_2") (pintype "input"))
      (node (ref "J250") (pin "2") (pinfunction "2_2") (pintype "input"))
    )
    (net (code "87") (name "Net-(D263-A)") (class "Default")
      (node (ref "D263") (pin "2") (pinfunction "A_2") (pintype "input"))
      (node (ref "J251") (pin "2") (pinfunction "2_2") (pintype "input"))
    )
    (net (code "88") (name "Net-(D264-A)") (class "Default")
      (node (ref "D264") (pin "2") (pinfunction "A_2") (pintype "input"))
      (node (ref "J252") (pin "2") (pinfunction "2_2") (pintype "input"))
    )
    (net (code "89") (name "Net-(D265-A)") (class "Default")
      (node (ref "D265") (pin "2") (pinfunction "A_2") (pintype "input"))
      (node (ref "J253") (pin "2") (pinfunction "2_2") (pintype "input"))
    )
    (net (code "90") (name "Net-(D266-A)") (class "Default")
      (node (ref "D266") (pin "2") (pinfunction "A_2") (pintype "input"))
      (node (ref "J254") (pin "2") (pinfunction "2_2") (pintype "input"))
    )
    (net (code "91") (name "Net-(D267-A)") (class "Default")
      (node (ref "D267") (pin "2") (pinfunction "A_2") (pintype "input"))
      (node (ref "J255") (pin "2") (pinfunction "2_2") (pintype "input"))
    )
    (net (code "92") (name "Net-(D268-A)") (class "Default")
      (node (ref "D268") (pin "2") (pinfunction "A_2") (pintype "input"))
      (node (ref "J256") (pin "2") (pinfunction "2_2") (pintype "input"))
    )
    (net (code "93") (name "Net-(D269-A)") (class "Default")
      (node (ref "D269") (pin "2") (pinfunction "A_2") (pintype "input"))
      (node (ref "J257") (pin "2") (pinfunction "2_2") (pintype "input"))
    )
    (net (code "94") (name "Net-(D270-A)") (class "Default")
      (node (ref "D270") (pin "2") (pinfunction "A_2") (pintype "input"))
      (node (ref "J258") (pin "2") (pinfunction "2_2") (pintype "input"))
    )
    (net (code "95") (name "Net-(D271-A)") (class "Default")
      (node (ref "D271") (pin "2") (pinfunction "A_2") (pintype "input"))
      (node (ref "J259") (pin "2") (pinfunction "2_2") (pintype "input"))
    )
    (net (code "96") (name "Net-(D272-A)") (class "Default")
      (node (ref "D272") (pin "2") (pinfunction "A_2") (pintype "input"))
      (node (ref "J260") (pin "2") (pinfunction "2_2") (pintype "input"))
    )
    (net (code "97") (name "Net-(D273-A)") (class "Default")
      (node (ref "D273") (pin "2") (pinfunction "A_2") (pintype "input"))
      (node (ref "J261") (pin "2") (pinfunction "2_2") (pintype "input"))
    )
    (net (code "98") (name "Net-(D274-A)") (class "Default")
      (node (ref "D274") (pin "2") (pinfunction "A_2") (pintype "input"))
      (node (ref "J262") (pin "2") (pinfunction "2_2") (pintype "input"))
    )
    (net (code "99") (name "Net-(D275-A)") (class "Default")
      (node (ref "D275") (pin "2") (pinfunction "A_2") (pintype "input"))
      (node (ref "J263") (pin "2") (pinfunction "2_2") (pintype "input"))
    )
    (net (code "100") (name "Net-(D276-A)") (class "Default")
      (node (ref "D276") (pin "2") (pinfunction "A_2") (pintype "input"))
      (node (ref "J264") (pin "2") (pinfunction "2_2") (pintype "input"))
    )
    (net (code "101") (name "Net-(D277-A)") (class "Default")
      (node (ref "D277") (pin "2") (pinfunction "A_2") (pintype "input"))
      (node (ref "J265") (pin "2") (pinfunction "2_2") (pintype "input"))
    )
    (net (code "102") (name "Net-(D278-A)") (class "Default")
      (node (ref "D278") (pin "2") (pinfunction "A_2") (pintype "input"))
      (node (ref "J266") (pin "2") (pinfunction "2_2") (pintype "input"))
    )
    (net (code "103") (name "Net-(D279-A)") (class "Default")
      (node (ref "D279") (pin "2") (pinfunction "A_2") (pintype "input"))
      (node (ref "J267") (pin "2") (pinfunction "2_2") (pintype "input"))
    )
    (net (code "104") (name "Net-(D280-A)") (class "Default")
      (node (ref "D280") (pin "2") (pinfunction "A_2") (pintype "input"))
      (node (ref "J268") (pin "2") (pinfunction "2_2") (pintype "input"))
    )
    (net (code "105") (name "Net-(D281-A)") (class "Default")
      (node (ref "D281") (pin "2") (pinfunction "A_2") (pintype "input"))
      (node (ref "J269") (pin "2") (pinfunction "2_2") (pintype "input"))
    )
    (net (code "106") (name "Net-(D282-A)") (class "Default")
      (node (ref "D282") (pin "2") (pinfunction "A_2") (pintype "input"))
      (node (ref "J270") (pin "2") (pinfunction "2_2") (pintype "input"))
    )
    (net (code "107") (name "Net-(D283-A)") (class "Default")
      (node (ref "D283") (pin "2") (pinfunction "A_2") (pintype "input"))
      (node (ref "J271") (pin "2") (pinfunction "2_2") (pintype "input"))
    )
    (net (code "108") (name "Net-(D284-A)") (class "Default")
      (node (ref "D284") (pin "2") (pinfunction "A_2") (pintype "input"))
      (node (ref "J272") (pin "2") (pinfunction "2_2") (pintype "input"))
    )
    (net (code "109") (name "Net-(D285-A)") (class "Default")
      (node (ref "D285") (pin "2") (pinfunction "A_2") (pintype "input"))
      (node (ref "J273") (pin "2") (pinfunction "2_2") (pintype "input"))
    )
    (net (code "110") (name "Net-(D286-A)") (class "Default")
      (node (ref "D286") (pin "2") (pinfunction "A_2") (pintype "input"))
      (node (ref "J274") (pin "2") (pinfunction "2_2") (pintype "input"))
    )
    (net (code "111") (name "Net-(D287-A)") (class "Default")
      (node (ref "D287") (pin "2") (pinfunction "A_2") (pintype "input"))
      (node (ref "J275") (pin "2") (pinfunction "2_2") (pintype "input"))
    )
    (net (code "112") (name "Net-(D288-A)") (class "Default")
      (node (ref "D288") (pin "2") (pinfunction "A_2") (pintype "input"))
      (node (ref "J276") (pin "2") (pinfunction "2_2") (pintype "input"))
    )
    (net (code "113") (name "Net-(D289-A)") (class "Default")
      (node (ref "D289") (pin "2") (pinfunction "A_2") (pintype "input"))
      (node (ref "J277") (pin "2") (pinfunction "2_2") (pintype "input"))
    )
    (net (code "114") (name "Net-(D290-A)") (class "Default")
      (node (ref "D290") (pin "2") (pinfunction "A_2") (pintype "input"))
      (node (ref "J278") (pin "2") (pinfunction "2_2") (pintype "input"))
    )
    (net (code "115") (name "Net-(ENC201-PadA)") (class "Default")
      (node (ref "ENC201") (pin "A") (pinfunction "A_A") (pintype "input"))
      (node (ref "R201") (pin "1") (pinfunction "1_1") (pintype "input"))
      (node (ref "R205") (pin "2") (pinfunction "2_2") (pintype "input"))
    )
    (net (code "116") (name "Net-(ENC201-PadB)") (class "Default")
      (node (ref "ENC201") (pin "B") (pinfunction "B_B") (pintype "input"))
      (node (ref "R202") (pin "1") (pinfunction "1_1") (pintype "input"))
      (node (ref "R207") (pin "2") (pinfunction "2_2") (pintype "input"))
    )
    (net (code "117") (name "Net-(FPC1-Pad7)") (class "Default")
      (node (ref "FPC1") (pin "7") (pinfunction "7_7") (pintype "unspecified"))
      (node (ref "R223") (pin "1") (pinfunction "1_1") (pintype "input"))
    )
    (net (code "118") (name "Net-(FPC1-Pad9)") (class "Default")
      (node (ref "FPC1") (pin "9") (pinfunction "9_9") (pintype "unspecified"))
      (node (ref "R224") (pin "1") (pinfunction "1_1") (pintype "input"))
    )
    (net (code "119") (name "Net-(J101-CC1)") (class "Default")
      (node (ref "J101") (pin "4") (pinfunction "CC1_4") (pintype "unspecified"))
      (node (ref "R119") (pin "2") (pinfunction "2_2") (pintype "input"))
    )
    (net (code "120") (name "Net-(J101-CC2)") (class "Default")
      (node (ref "J101") (pin "10") (pinfunction "CC2_10") (pintype "unspecified"))
      (node (ref "R118") (pin "2") (pinfunction "2_2") (pintype "input"))
    )
    (net (code "121") (name "Net-(LED102-A)") (class "Default")
      (node (ref "LED102") (pin "1") (pinfunction "A_1") (pintype "unspecified"))
      (node (ref "R104") (pin "1") (pinfunction "1_1") (pintype "input"))
    )
    (net (code "122") (name "Net-(SW101-C)") (class "Default")
      (node (ref "R122") (pin "1") (pinfunction "1_1") (pintype "input"))
      (node (ref "R124") (pin "1") (pinfunction "1_1") (pintype "input"))
      (node (ref "SW101") (pin "3") (pinfunction "C_3") (pintype "input"))
      (node (ref "SW101") (pin "4") (pinfunction "D_4") (pintype "input"))
    )
    (net (code "123") (name "Net-(SW102-C)") (class "Default")
      (node (ref "R123") (pin "1") (pinfunction "1_1") (pintype "input"))
      (node (ref "R125") (pin "1") (pinfunction "1_1") (pintype "input"))
      (node (ref "SW102") (pin "3") (pinfunction "C_3") (pintype "input"))
      (node (ref "SW102") (pin "4") (pinfunction "D_4") (pintype "input"))
    )
    (net (code "124") (name "QSPI_SCLK") (class "Default")
      (node (ref "U101") (pin "52") (pinfunction "QSPI_SCLK_52") (pintype "output"))
      (node (ref "U104") (pin "6") (pinfunction "CLK_6") (pintype "unspecified"))
    )
    (net (code "125") (name "QSPI_SD0") (class "Default")
      (node (ref "U101") (pin "53") (pinfunction "QSPI_SD0_53") (pintype "bidirectional"))
      (node (ref "U104") (pin "5") (pinfunction "DI_5") (pintype "unspecified"))
    )
    (net (code "126") (name "QSPI_SD1") (class "Default")
      (node (ref "U101") (pin "55") (pinfunction "QSPI_SD1_55") (pintype "bidirectional"))
      (node (ref "U104") (pin "2") (pinfunction "DO_2") (pintype "unspecified"))
    )
    (net (code "127") (name "QSPI_SD2") (class "Default")
      (node (ref "U101") (pin "54") (pinfunction "QSPI_SD2_54") (pintype "bidirectional"))
      (node (ref "U104") (pin "3") (pinfunction "IO2_3") (pintype "unspecified"))
    )
    (net (code "128") (name "QSPI_SD3") (class "Default")
      (node (ref "U101") (pin "51") (pinfunction "QSPI_SD3_51") (pintype "bidirectional"))
      (node (ref "U104") (pin "7") (pinfunction "IO3_7") (pintype "unspecified"))
    )
    (net (code "129") (name "QSPI_SS") (class "Default")
      (node (ref "R124") (pin "2") (pinfunction "2_2") (pintype "input"))
      (node (ref "U101") (pin "56") (pinfunction "QSPI_SS_56") (pintype "bidirectional"))
      (node (ref "U104") (pin "1") (pinfunction "CS#_1") (pintype "unspecified"))
    )
    (net (code "130") (name "RESET_N") (class "Default")
      (node (ref "C127") (pin "2") (pinfunction "2_2") (pintype "unspecified"))
      (node (ref "R125") (pin "2") (pinfunction "2_2") (pintype "input"))
      (node (ref "U101") (pin "26") (pinfunction "RUN_26") (pintype "input"))
    )
    (net (code "131") (name "ROW0") (class "Default")
      (node (ref "D201") (pin "1") (pinfunction "K_1") (pintype "input"))
      (node (ref "D202") (pin "1") (pinfunction "K_1") (pintype "input"))
      (node (ref "D203") (pin "1") (pinfunction "K_1") (pintype "input"))
      (node (ref "D213") (pin "1") (pinfunction "K_1") (pintype "input"))
      (node (ref "D214") (pin "1") (pinfunction "K_1") (pintype "input"))
      (node (ref "D215") (pin "1") (pinfunction "K_1") (pintype "input"))
      (node (ref "D225") (pin "1") (pinfunction "K_1") (pintype "input"))
      (node (ref "D226") (pin "1") (pinfunction "K_1") (pintype "input"))
      (node (ref "D227") (pin "1") (pinfunction "K_1") (pintype "input"))
      (node (ref "D237") (pin "1") (pinfunction "K_1") (pintype "input"))
      (node (ref "D238") (pin "1") (pinfunction "K_1") (pintype "input"))
      (node (ref "D239") (pin "1") (pinfunction "K_1") (pintype "input"))
      (node (ref "D249") (pin "1") (pinfunction "K_1") (pintype "input"))
      (node (ref "R217") (pin "2") (pinfunction "2_2") (pintype "input"))
    )
    (net (code "132") (name "ROW0_R") (class "Default")
      (node (ref "R217") (pin "1") (pinfunction "1_1") (pintype "input"))
      (node (ref "U101") (pin "16") (pinfunction "GPIO13_16") (pintype "bidirectional"))
    )
    (net (code "133") (name "ROW1") (class "Default")
      (node (ref "D204") (pin "1") (pinfunction "K_1") (pintype "input"))
      (node (ref "D205") (pin "1") (pinfunction "K_1") (pintype "input"))
      (node (ref "D206") (pin "1") (pinfunction "K_1") (pintype "input"))
      (node (ref "D216") (pin "1") (pinfunction "K_1") (pintype "input"))
      (node (ref "D217") (pin "1") (pinfunction "K_1") (pintype "input"))
      (node (ref "D218") (pin "1") (pinfunction "K_1") (pintype "input"))
      (node (ref "D228") (pin "1") (pinfunction "K_1") (pintype "input"))
      (node (ref "D229") (pin "1") (pinfunction "K_1") (pintype "input"))
      (node (ref "D230") (pin "1") (pinfunction "K_1") (pintype "input"))
      (node (ref "D240") (pin "1") (pinfunction "K_1") (pintype "input"))
      (node (ref "D241") (pin "1") (pinfunction "K_1") (pintype "input"))
      (node (ref "D242") (pin "1") (pinfunction "K_1") (pintype "input"))
      (node (ref "D250") (pin "1") (pinfunction "K_1") (pintype "input"))
      (node (ref "R218") (pin "2") (pinfunction "2_2") (pintype "input"))
    )
    (net (code "134") (name "ROW1_R") (class "Default")
      (node (ref "R218") (pin "1") (pinfunction "1_1") (pintype "input"))
      (node (ref "U101") (pin "17") (pinfunction "GPIO14_17") (pintype "bidirectional"))
    )
    (net (code "135") (name "ROW2") (class "Default")
      (node (ref "D207") (pin "1") (pinfunction "K_1") (pintype "input"))
      (node (ref "D208") (pin "1") (pinfunction "K_1") (pintype "input"))
      (node (ref "D209") (pin "1") (pinfunction "K_1") (pintype "input"))
      (node (ref "D219") (pin "1") (pinfunction "K_1") (pintype "input"))
      (node (ref "D220") (pin "1") (pinfunction "K_1") (pintype "input"))
      (node (ref "D221") (pin "1") (pinfunction "K_1") (pintype "input"))
      (node (ref "D231") (pin "1") (pinfunction "K_1") (pintype "input"))
      (node (ref "D232") (pin "1") (pinfunction "K_1") (pintype "input"))
      (node (ref "D233") (pin "1") (pinfunction "K_1") (pintype "input"))
      (node (ref "D243") (pin "1") (pinfunction "K_1") (pintype "input"))
      (node (ref "D244") (pin "1") (pinfunction "K_1") (pintype "input"))
      (node (ref "D245") (pin "1") (pinfunction "K_1") (pintype "input"))
      (node (ref "D251") (pin "1") (pinfunction "K_1") (pintype "input"))
      (node (ref "R219") (pin "2") (pinfunction "2_2") (pintype "input"))
    )
    (net (code "136") (name "ROW2_R") (class "Default")
      (node (ref "R219") (pin "1") (pinfunction "1_1") (pintype "input"))
      (node (ref "U101") (pin "18") (pinfunction "GPIO15_18") (pintype "bidirectional"))
    )
    (net (code "137") (name "ROW3") (class "Default")
      (node (ref "D252") (pin "1") (pinfunction "K_1") (pintype "input"))
      (node (ref "D253") (pin "1") (pinfunction "K_1") (pintype "input"))
      (node (ref "D254") (pin "1") (pinfunction "K_1") (pintype "input"))
      (node (ref "D261") (pin "1") (pinfunction "K_1") (pintype "input"))
      (node (ref "D262") (pin "1") (pinfunction "K_1") (pintype "input"))
      (node (ref "D263") (pin "1") (pinfunction "K_1") (pintype "input"))
      (node (ref "D270") (pin "1") (pinfunction "K_1") (pintype "input"))
      (node (ref "D271") (pin "1") (pinfunction "K_1") (pintype "input"))
      (node (ref "D272") (pin "1") (pinfunction "K_1") (pintype "input"))
      (node (ref "D279") (pin "1") (pinfunction "K_1") (pintype "input"))
      (node (ref "D280") (pin "1") (pinfunction "K_1") (pintype "input"))
      (node (ref "D281") (pin "1") (pinfunction "K_1") (pintype "input"))
      (node (ref "D288") (pin "1") (pinfunction "K_1") (pintype "input"))
      (node (ref "R220") (pin "2") (pinfunction "2_2") (pintype "input"))
    )
    (net (code "138") (name "ROW3_R") (class "Default")
      (node (ref "R220") (pin "1") (pinfunction "1_1") (pintype "input"))
      (node (ref "U101") (pin "27") (pinfunction "GPIO16_27") (pintype "bidirectional"))
    )
    (net (code "139") (name "ROW4") (class "Default")
      (node (ref "D255") (pin "1") (pinfunction "K_1") (pintype "input"))
      (node (ref "D256") (pin "1") (pinfunction "K_1") (pintype "input"))
      (node (ref "D257") (pin "1") (pinfunction "K_1") (pintype "input"))
      (node (ref "D264") (pin "1") (pinfunction "K_1") (pintype "input"))
      (node (ref "D265") (pin "1") (pinfunction "K_1") (pintype "input"))
      (node (ref "D266") (pin "1") (pinfunction "K_1") (pintype "input"))
      (node (ref "D273") (pin "1") (pinfunction "K_1") (pintype "input"))
      (node (ref "D274") (pin "1") (pinfunction "K_1") (pintype "input"))
      (node (ref "D275") (pin "1") (pinfunction "K_1") (pintype "input"))
      (node (ref "D282") (pin "1") (pinfunction "K_1") (pintype "input"))
      (node (ref "D283") (pin "1") (pinfunction "K_1") (pintype "input"))
      (node (ref "D284") (pin "1") (pinfunction "K_1") (pintype "input"))
      (node (ref "D289") (pin "1") (pinfunction "K_1") (pintype "input"))
      (node (ref "R221") (pin "2") (pinfunction "2_2") (pintype "input"))
    )
    (net (code "140") (name "ROW4_R") (class "Default")
      (node (ref "R221") (pin "1") (pinfunction "1_1") (pintype "input"))
      (node (ref "U101") (pin "28") (pinfunction "GPIO17_28") (pintype "bidirectional"))
    )
    (net (code "141") (name "ROW5") (class "Default")
      (node (ref "D258") (pin "1") (pinfunction "K_1") (pintype "input"))
      (node (ref "D259") (pin "1") (pinfunction "K_1") (pintype "input"))
      (node (ref "D260") (pin "1") (pinfunction "K_1") (pintype "input"))
      (node (ref "D267") (pin "1") (pinfunction "K_1") (pintype "input"))
      (node (ref "D268") (pin "1") (pinfunction "K_1") (pintype "input"))
      (node (ref "D269") (pin "1") (pinfunction "K_1") (pintype "input"))
      (node (ref "D276") (pin "1") (pinfunction "K_1") (pintype "input"))
      (node (ref "D277") (pin "1") (pinfunction "K_1") (pintype "input"))
      (node (ref "D278") (pin "1") (pinfunction "K_1") (pintype "input"))
      (node (ref "D285") (pin "1") (pinfunction "K_1") (pintype "input"))
      (node (ref "D286") (pin "1") (pinfunction "K_1") (pintype "input"))
      (node (ref "D287") (pin "1") (pinfunction "K_1") (pintype "input"))
      (node (ref "D290") (pin "1") (pinfunction "K_1") (pintype "input"))
      (node (ref "R222") (pin "2") (pinfunction "2_2") (pintype "input"))
    )
    (net (code "142") (name "ROW5_R") (class "Default")
      (node (ref "R222") (pin "1") (pinfunction "1_1") (pintype "input"))
      (node (ref "U101") (pin "29") (pinfunction "GPIO18_29") (pintype "bidirectional"))
    )
    (net (code "143") (name "RS") (class "Default")
      (node (ref "FPC1") (pin "3") (pinfunction "3_3") (pintype "unspecified"))
      (node (ref "U101") (pin "34") (pinfunction "GPIO22_34") (pintype "bidirectional"))
    )
    (net (code "144") (name "RSTB") (class "Default")
      (node (ref "FPC1") (pin "4") (pinfunction "4_4") (pintype "unspecified"))
      (node (ref "U101") (pin "40") (pinfunction "GPIO28_ADC2_40") (pintype "bidirectional"))
    )
    (net (code "145") (name "SCL") (class "Default")
      (node (ref "FPC1") (pin "2") (pinfunction "2_2") (pintype "unspecified"))
      (node (ref "U101") (pin "39") (pinfunction "GPIO27_ADC1_39") (pintype "bidirectional"))
    )
    (net (code "146") (name "SDA") (class "Default")
      (node (ref "FPC1") (pin "1") (pinfunction "1_1") (pintype "unspecified"))
      (node (ref "U101") (pin "38") (pinfunction "GPIO26_ADC0_38") (pintype "bidirectional"))
    )
    (net (code "147") (name "SWCLK") (class "Default")
      (node (ref "J102") (pin "1") (pinfunction "1_1") (pintype "input"))
      (node (ref "U101") (pin "24") (pinfunction "SWCLK_24") (pintype "output"))
    )
    (net (code "148") (name "SWDIO") (class "Default")
      (node (ref "J102") (pin "3") (pinfunction "3_3") (pintype "input"))
      (node (ref "U101") (pin "25") (pinfunction "SWD_25") (pintype "bidirectional"))
    )
    (net (code "149") (name "TE") (class "Default")
      (node (ref "FPC1") (pin "6") (pinfunction "6_6") (pintype "unspecified"))
      (node (ref "U101") (pin "41") (pinfunction "GPIO29_ADC3_41") (pintype "bidirectional"))
    )
    (net (code "150") (name "USB_N") (class "Default")
      (node (ref "R109") (pin "2") (pinfunction "2_2") (pintype "input"))
      (node (ref "U101") (pin "46") (pinfunction "USB_DM_46") (pintype "bidirectional"))
    )
    (net (code "151") (name "USB_P") (class "Default")
      (node (ref "R111") (pin "2") (pinfunction "2_2") (pintype "input"))
      (node (ref "U101") (pin "47") (pinfunction "USB_DP_47") (pintype "bidirectional"))
    )
    (net (code "152") (name "XIN") (class "Default")
      (node (ref "C123") (pin "1") (pinfunction "1_1") (pintype "unspecified"))
      (node (ref "R120") (pin "2") (pinfunction "2_2") (pintype "input"))
      (node (ref "U101") (pin "20") (pinfunction "XIN_20") (pintype "input"))
      (node (ref "Y101") (pin "1") (pinfunction "1_1") (pintype "input"))
    )
    (net (code "153") (name "XOUT") (class "Default")
      (node (ref "R120") (pin "1") (pinfunction "1_1") (pintype "input"))
      (node (ref "R121") (pin "2") (pinfunction "2_2") (pintype "input"))
      (node (ref "U101") (pin "21") (pinfunction "XOUT_21") (pintype "unspecified"))
    )
    (net (code "154") (name "X_R") (class "Default")
      (node (ref "C124") (pin "1") (pinfunction "1_1") (pintype "unspecified"))
      (node (ref "R121") (pin "1") (pinfunction "1_1") (pintype "input"))
      (node (ref "Y101") (pin "3") (pinfunction "3_3") (pintype "input"))
    )
    (net (code "155") (name "unconnected-(ENC201-Pad1)") (class "Default")
      (node (ref "ENC201") (pin "1") (pinfunction "1_1") (pintype "input+no_connect"))
    )
    (net (code "156") (name "unconnected-(ENC201-Pad2)") (class "Default")
      (node (ref "ENC201") (pin "2") (pinfunction "2_2") (pintype "input+no_connect"))
    )
    (net (code "157") (name "unconnected-(FPC1-Pad11)") (class "Default")
      (node (ref "FPC1") (pin "11") (pinfunction "11_11") (pintype "unspecified+no_connect"))
    )
    (net (code "158") (name "unconnected-(FPC1-Pad12)") (class "Default")
      (node (ref "FPC1") (pin "12") (pinfunction "12_12") (pintype "unspecified+no_connect"))
    )
    (net (code "159") (name "unconnected-(J101-SBU1-Pad9)") (class "Default")
      (node (ref "J101") (pin "9") (pinfunction "SBU1_9") (pintype "unspecified+no_connect"))
    )
    (net (code "160") (name "unconnected-(J101-SBU2-Pad3)") (class "Default")
      (node (ref "J101") (pin "3") (pinfunction "SBU2_3") (pintype "unspecified+no_connect"))
    )
    (net (code "161") (name "unconnected-(U101-GPIO23-Pad35)") (class "Default")
      (node (ref "U101") (pin "35") (pinfunction "GPIO23_35") (pintype "bidirectional+no_connect"))
    )
    (net (code "162") (name "unconnected-(U101-GPIO24-Pad36)") (class "Default")
      (node (ref "U101") (pin "36") (pinfunction "GPIO24_36") (pintype "bidirectional+no_connect"))
    )
    (net (code "163") (name "unconnected-(U101-GPIO25-Pad37)") (class "Default")
      (node (ref "U101") (pin "37") (pinfunction "GPIO25_37") (pintype "bidirectional+no_connect"))
    )
  )
)
